# RX08-.net
KiCad netlist of a schematic drawn in EAGLE
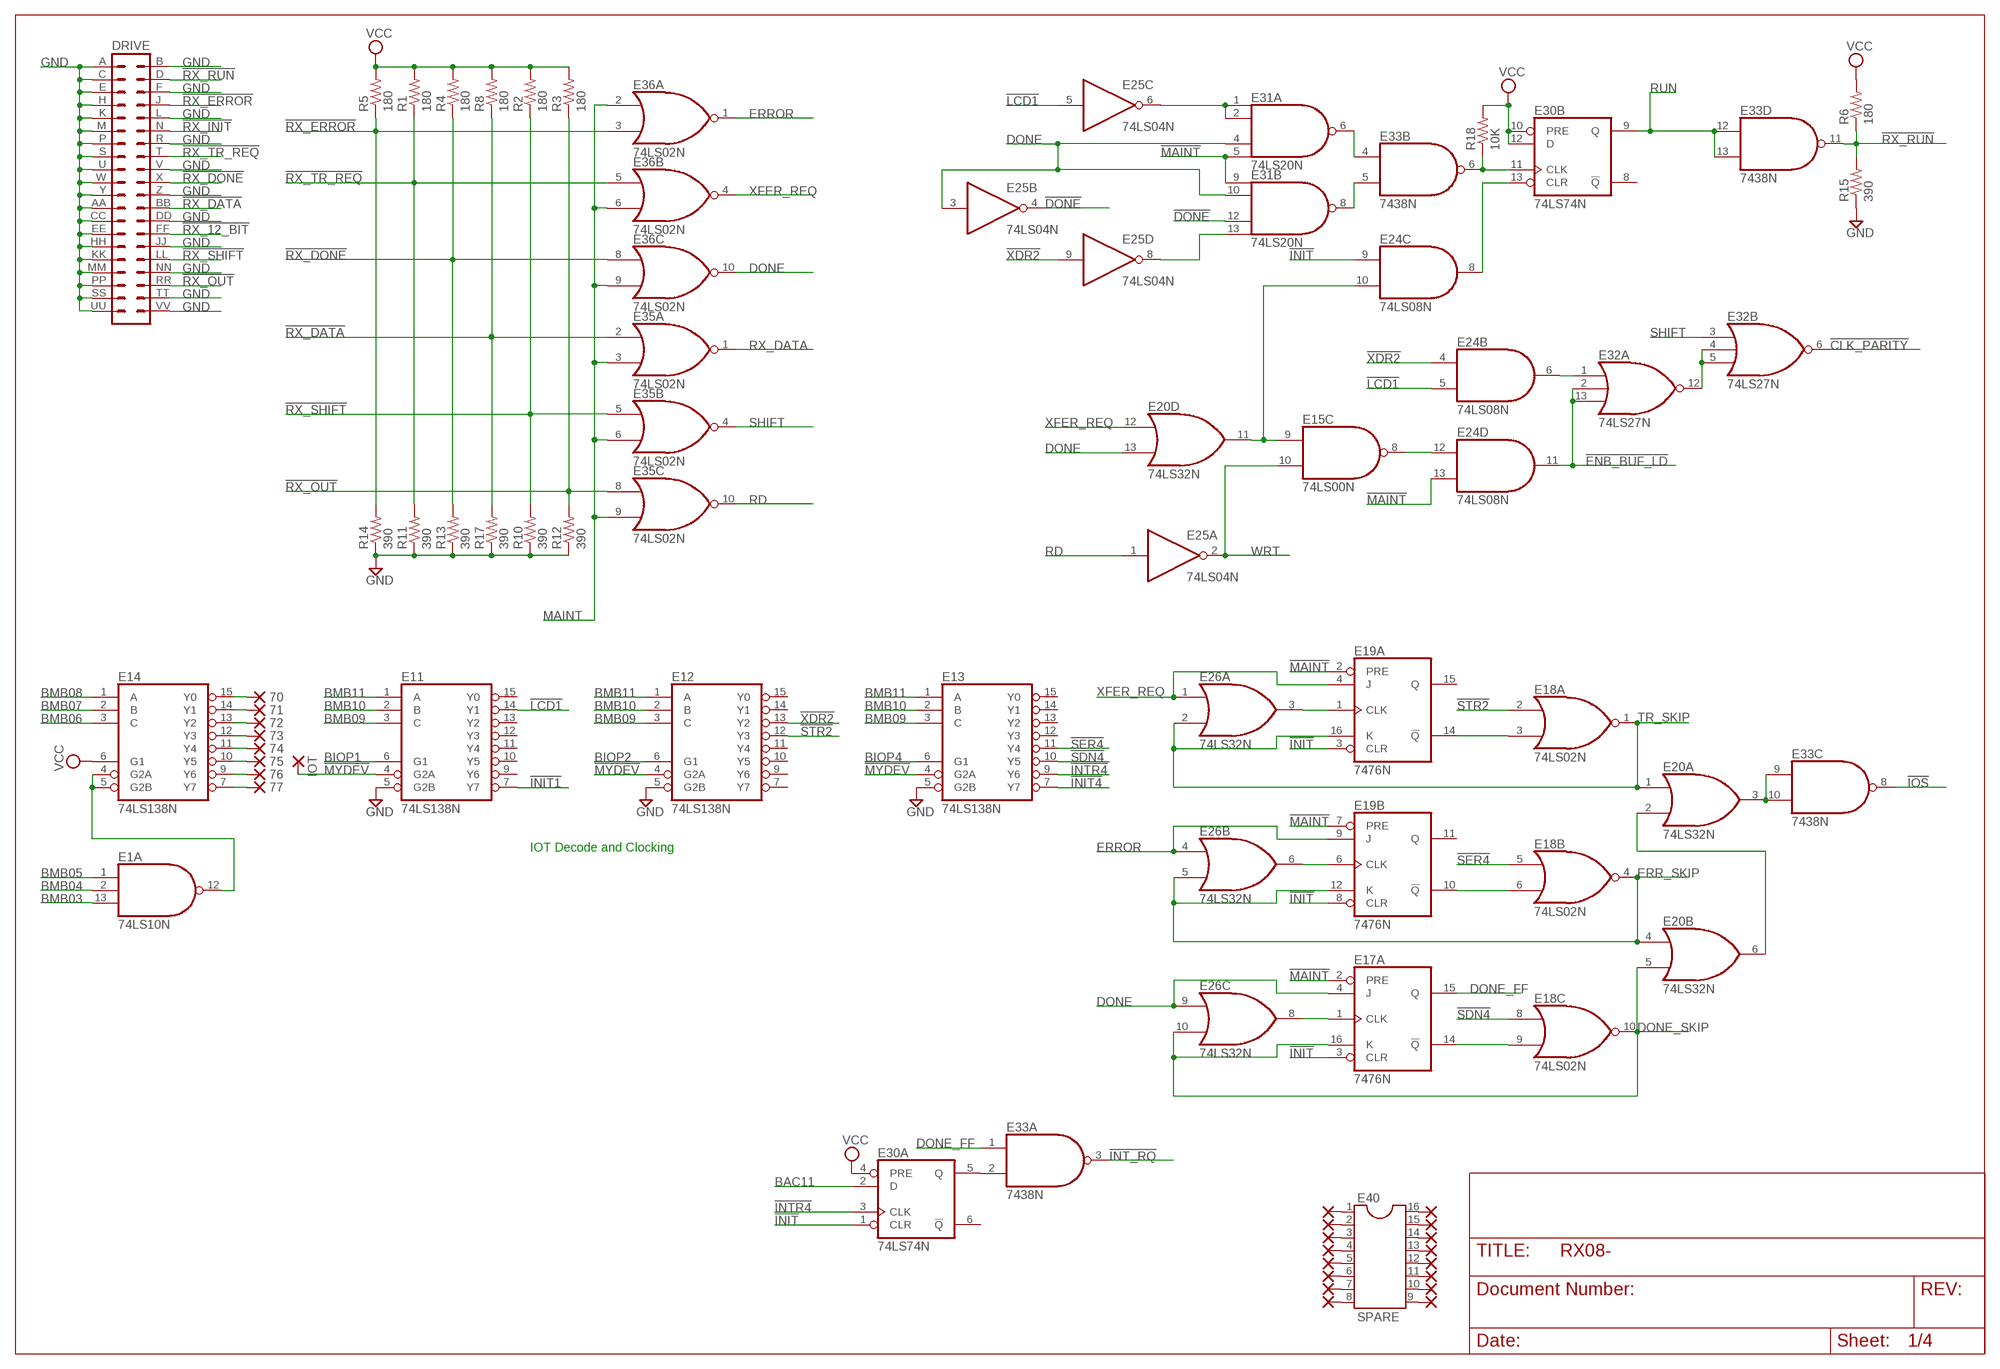
[diagram p0: schematic, sheet 1]
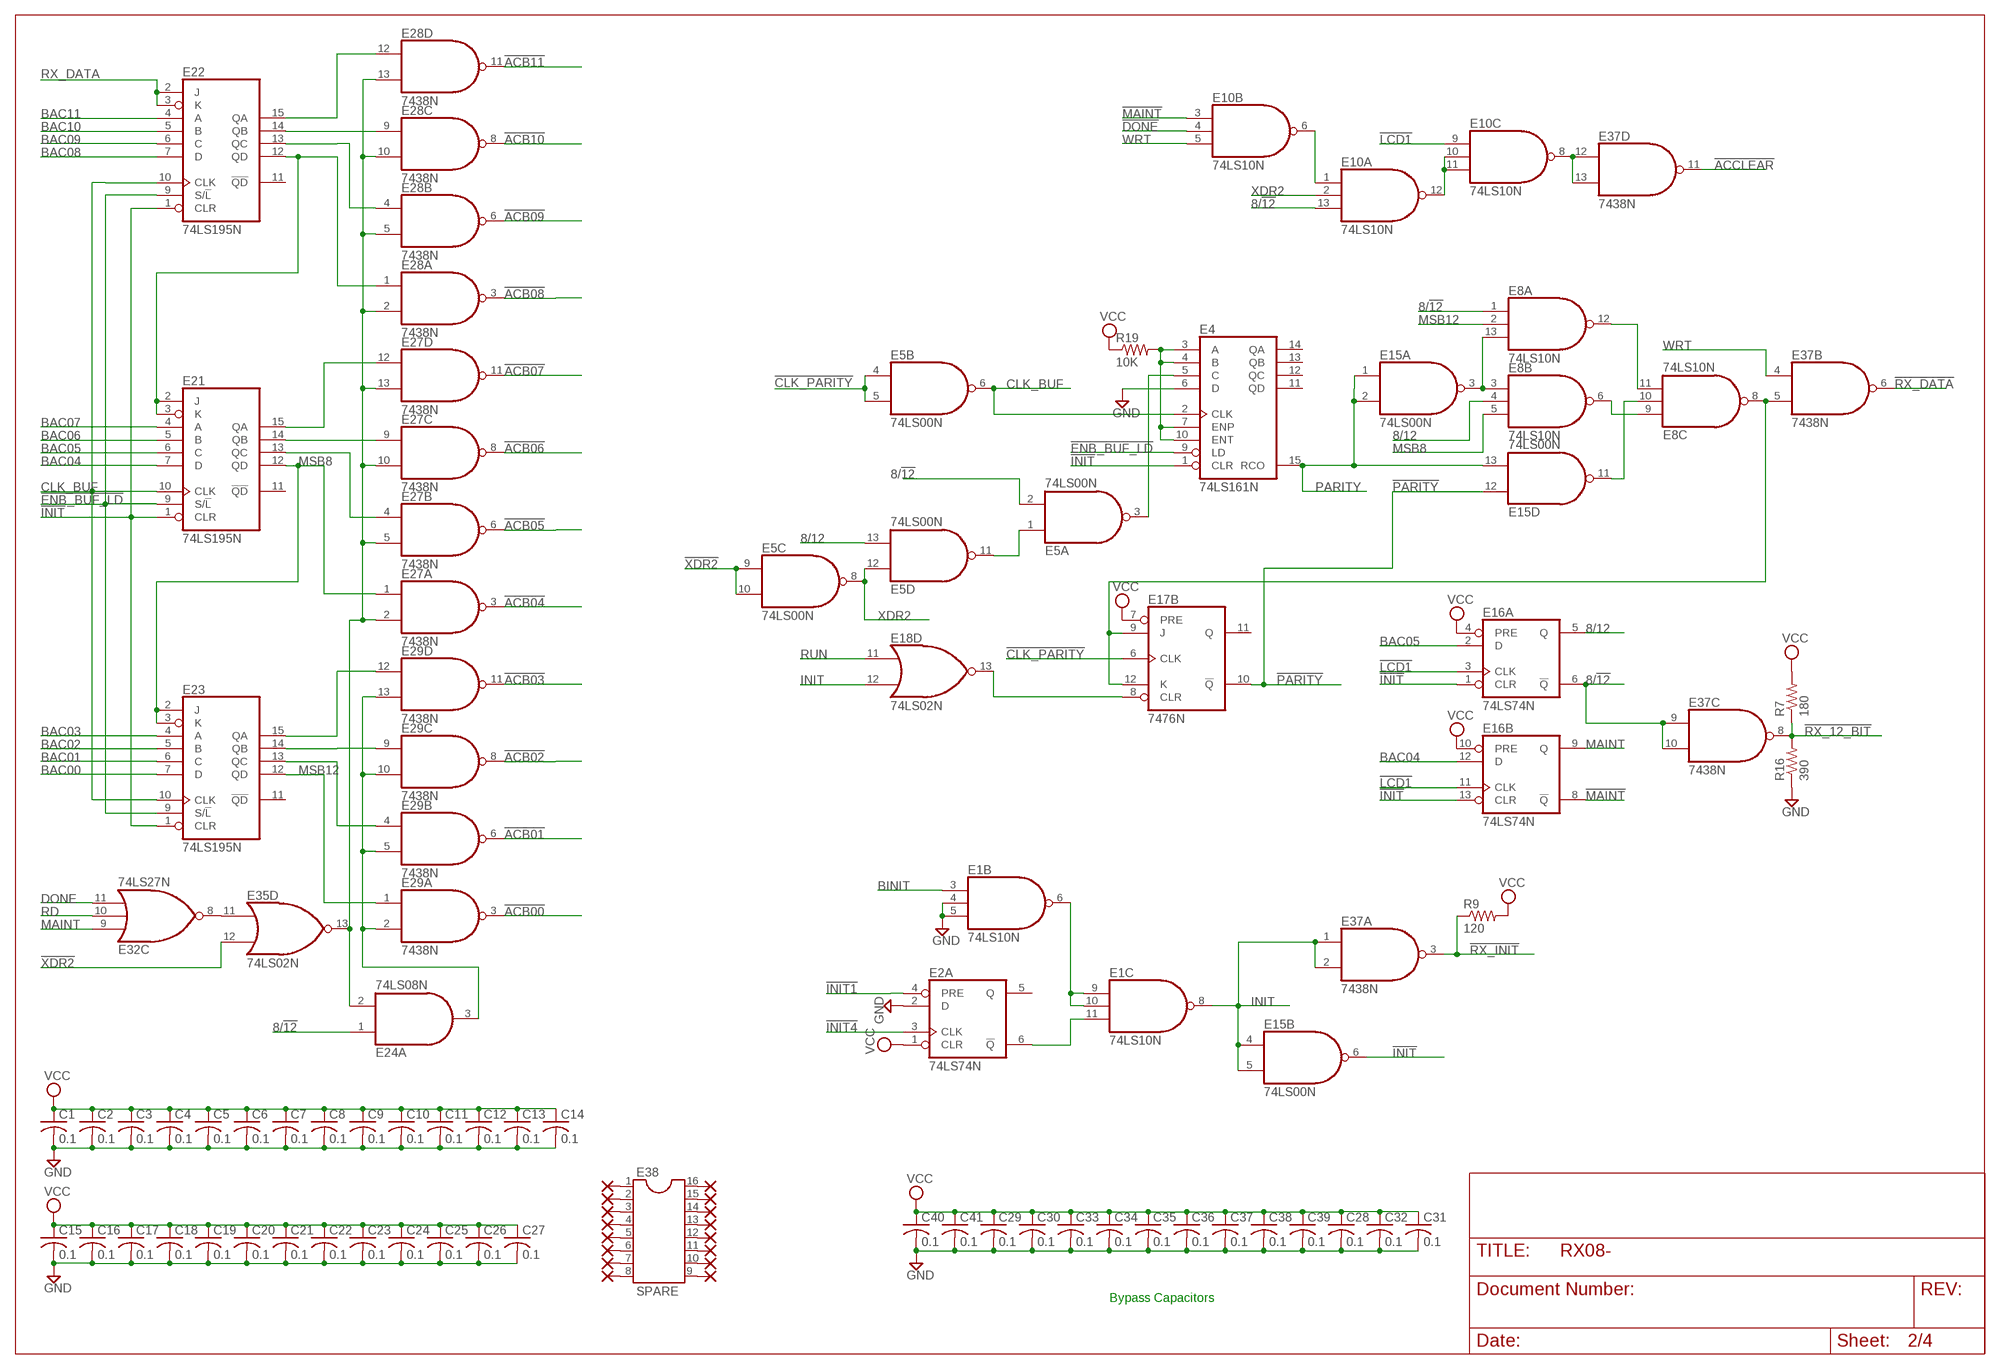
[diagram p1: schematic, sheet 2]
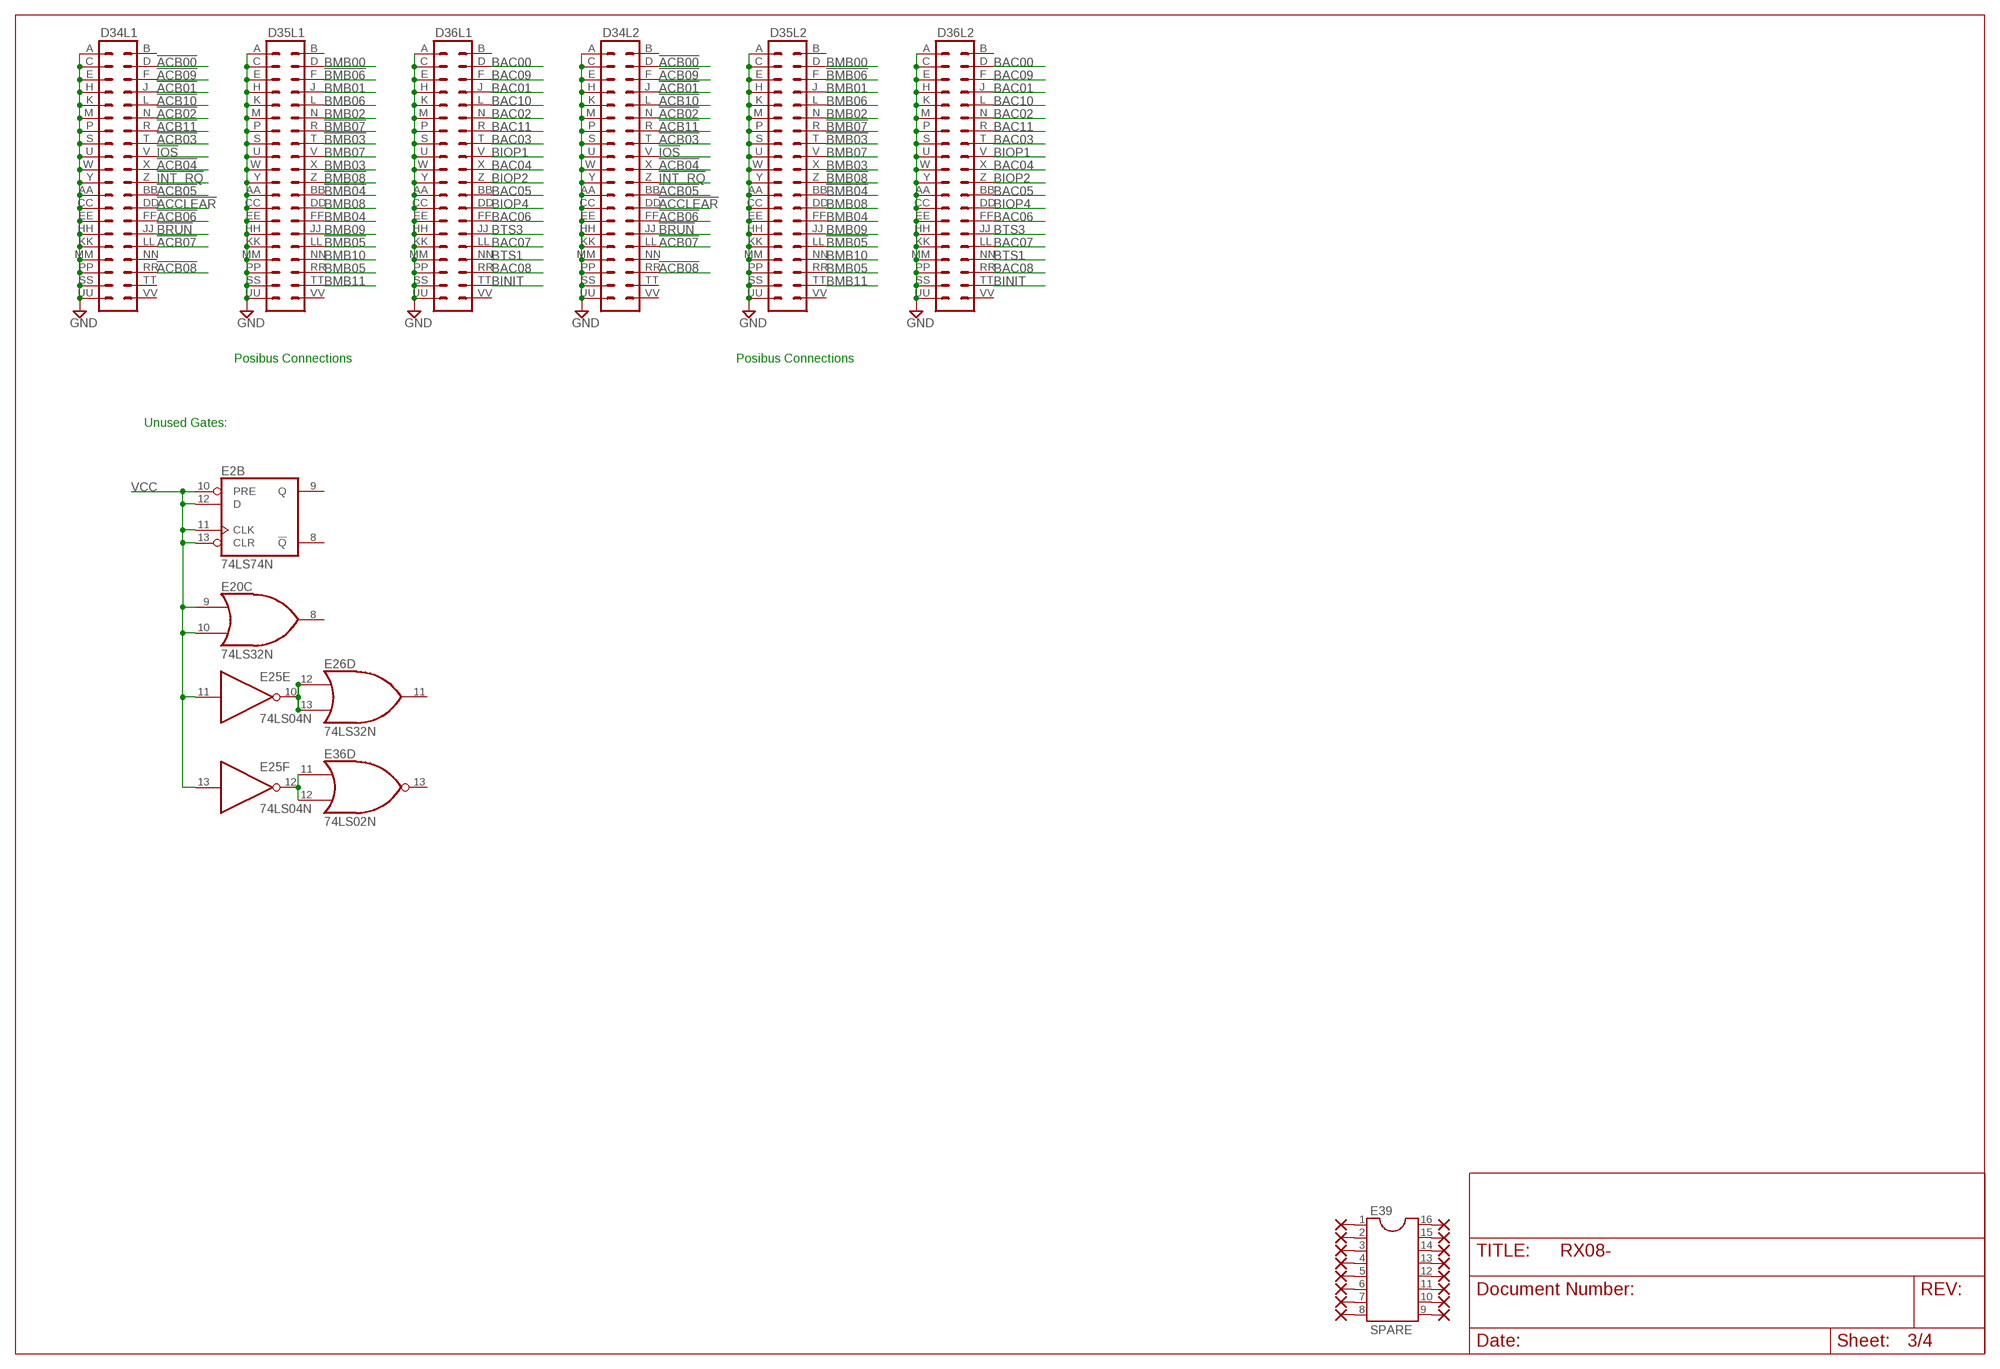
[diagram p2: schematic, sheet 3]
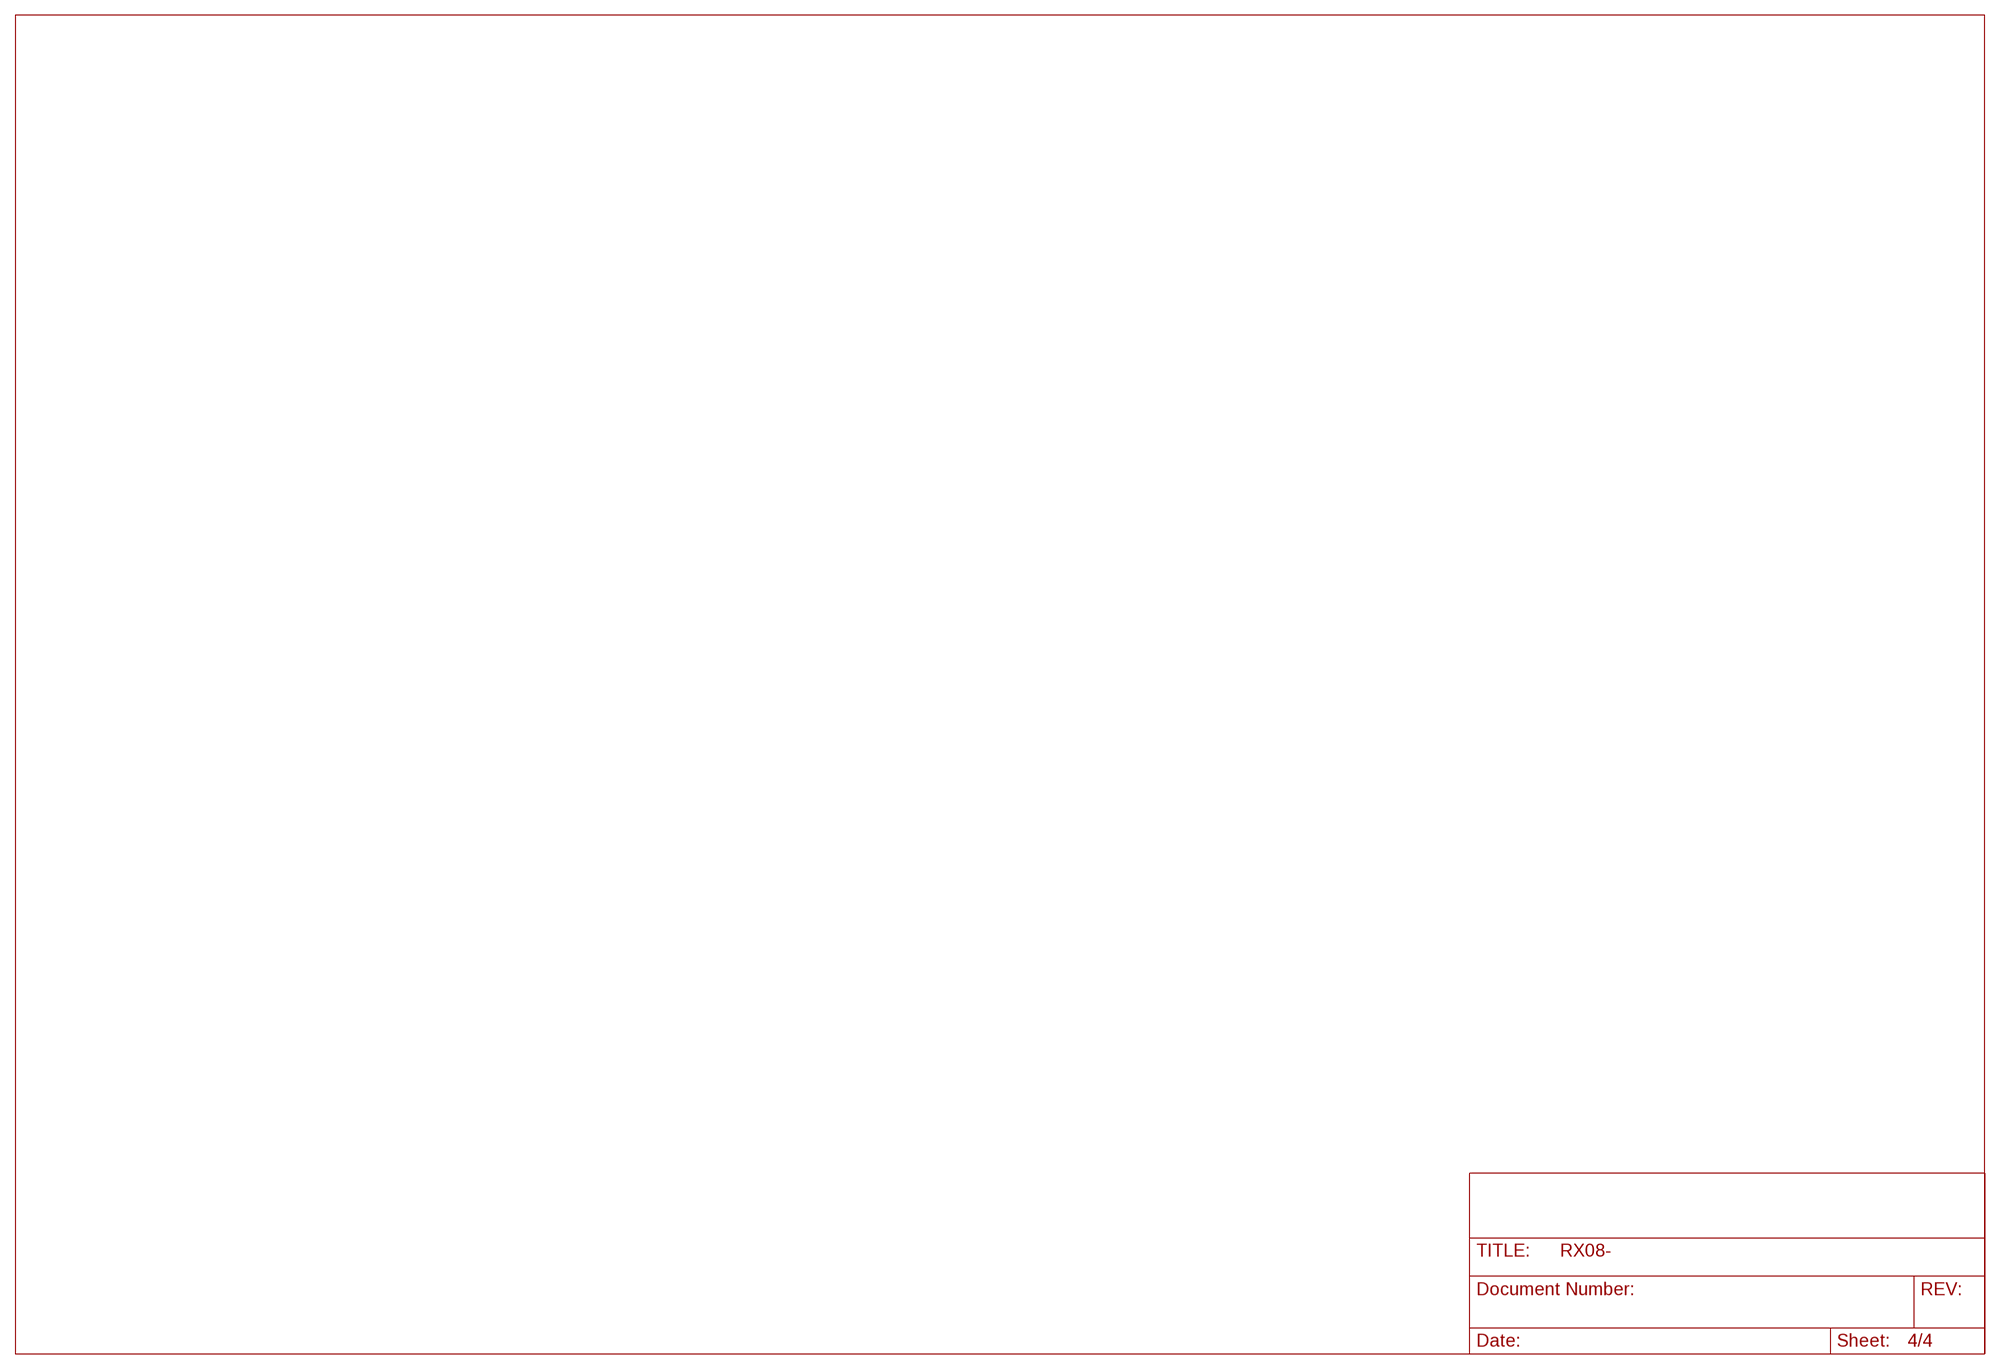
[diagram p3: schematic, sheet 4]

(export (version "E")
  (design (tool "Eeschema 10.0.6"))
  (components
    (comp (ref "70")
      (value "1,6/0,8")
      (footprint "eagle-import:1,6_0,8")
      (libsource (lib "eagle-import") (part "1,6/0,8"))
    )
    (comp (ref "71")
      (value "1,6/0,8")
      (footprint "eagle-import:1,6_0,8")
      (libsource (lib "eagle-import") (part "1,6/0,8"))
    )
    (comp (ref "72")
      (value "1,6/0,8")
      (footprint "eagle-import:1,6_0,8")
      (libsource (lib "eagle-import") (part "1,6/0,8"))
    )
    (comp (ref "73")
      (value "1,6/0,8")
      (footprint "eagle-import:1,6_0,8")
      (libsource (lib "eagle-import") (part "1,6/0,8"))
    )
    (comp (ref "74")
      (value "1,6/0,8")
      (footprint "eagle-import:1,6_0,8")
      (libsource (lib "eagle-import") (part "1,6/0,8"))
    )
    (comp (ref "75")
      (value "1,6/0,8")
      (footprint "eagle-import:1,6_0,8")
      (libsource (lib "eagle-import") (part "1,6/0,8"))
    )
    (comp (ref "76")
      (value "1,6/0,8")
      (footprint "eagle-import:1,6_0,8")
      (libsource (lib "eagle-import") (part "1,6/0,8"))
    )
    (comp (ref "77")
      (value "1,6/0,8")
      (footprint "eagle-import:1,6_0,8")
      (libsource (lib "eagle-import") (part "1,6/0,8"))
    )
    (comp (ref "DRIVE")
      (value "DEC40PINV")
      (footprint "eagle-import:DEC40PINV")
      (libsource (lib "eagle-import") (part "DEC40PINV"))
    )
    (comp (ref "E1")
      (value "74LS10N")
      (footprint "eagle-import:DIL14")
      (libsource (lib "eagle-import") (part "7410NLS"))
    )
    (comp (ref "E11")
      (value "74LS138N")
      (footprint "eagle-import:DIL16")
      (libsource (lib "eagle-import") (part "74138NLS"))
    )
    (comp (ref "E12")
      (value "74LS138N")
      (footprint "eagle-import:DIL16")
      (libsource (lib "eagle-import") (part "74138NLS"))
    )
    (comp (ref "E13")
      (value "74LS138N")
      (footprint "eagle-import:DIL16")
      (libsource (lib "eagle-import") (part "74138NLS"))
    )
    (comp (ref "E14")
      (value "74LS138N")
      (footprint "eagle-import:DIL16")
      (libsource (lib "eagle-import") (part "74138NLS"))
    )
    (comp (ref "E15")
      (value "74LS00N")
      (footprint "eagle-import:DIL14")
      (libsource (lib "eagle-import") (part "7400NLS"))
    )
    (comp (ref "E17")
      (value "7476N")
      (footprint "eagle-import:DIL16")
      (libsource (lib "eagle-import") (part "7476N"))
    )
    (comp (ref "E18")
      (value "74LS02N")
      (footprint "eagle-import:DIL14")
      (libsource (lib "eagle-import") (part "7402NLS"))
    )
    (comp (ref "E19")
      (value "7476N")
      (footprint "eagle-import:DIL16")
      (libsource (lib "eagle-import") (part "7476N"))
    )
    (comp (ref "E20")
      (value "74LS32N")
      (footprint "eagle-import:DIL14")
      (libsource (lib "eagle-import") (part "7432NLS"))
    )
    (comp (ref "E24")
      (value "74LS08N")
      (footprint "eagle-import:DIL14")
      (libsource (lib "eagle-import") (part "7408NLS"))
    )
    (comp (ref "E25")
      (value "74LS04N")
      (footprint "eagle-import:DIL14")
      (libsource (lib "eagle-import") (part "7404NLS"))
    )
    (comp (ref "E26")
      (value "74LS32N")
      (footprint "eagle-import:DIL14")
      (libsource (lib "eagle-import") (part "7432NLS"))
    )
    (comp (ref "E30")
      (value "74LS74N")
      (footprint "eagle-import:DIL14")
      (libsource (lib "eagle-import") (part "7474NLS"))
    )
    (comp (ref "E31")
      (value "74LS20N")
      (footprint "eagle-import:DIL14")
      (libsource (lib "eagle-import") (part "7420NLS"))
    )
    (comp (ref "E32")
      (value "74LS27N")
      (footprint "eagle-import:DIL14")
      (libsource (lib "eagle-import") (part "7427NLS"))
    )
    (comp (ref "E33")
      (value "7438N")
      (footprint "eagle-import:DIL14")
      (libsource (lib "eagle-import") (part "7438N"))
    )
    (comp (ref "E35")
      (value "74LS02N")
      (footprint "eagle-import:DIL14")
      (libsource (lib "eagle-import") (part "7402NLS"))
    )
    (comp (ref "E36")
      (value "74LS02N")
      (footprint "eagle-import:DIL14")
      (libsource (lib "eagle-import") (part "7402NLS"))
    )
    (comp (ref "E40")
      (value "SPARE")
      (footprint "eagle-import:DIL16")
      (libsource (lib "eagle-import") (part "DIL16"))
    )
    (comp (ref "IOT")
      (value "1,6/0,8")
      (footprint "eagle-import:1,6_0,8")
      (libsource (lib "eagle-import") (part "1,6/0,8"))
    )
    (comp (ref "PAD18")
      (value "1,6/0,8")
      (footprint "eagle-import:1,6_0,8")
      (libsource (lib "eagle-import") (part "1,6/0,8"))
    )
    (comp (ref "PAD19")
      (value "1,6/0,8")
      (footprint "eagle-import:1,6_0,8")
      (libsource (lib "eagle-import") (part "1,6/0,8"))
    )
    (comp (ref "PAD28")
      (value "1,6/0,8")
      (footprint "eagle-import:1,6_0,8")
      (libsource (lib "eagle-import") (part "1,6/0,8"))
    )
    (comp (ref "PAD29")
      (value "1,6/0,8")
      (footprint "eagle-import:1,6_0,8")
      (libsource (lib "eagle-import") (part "1,6/0,8"))
    )
    (comp (ref "PAD30")
      (value "1,6/0,8")
      (footprint "eagle-import:1,6_0,8")
      (libsource (lib "eagle-import") (part "1,6/0,8"))
    )
    (comp (ref "PAD31")
      (value "1,6/0,8")
      (footprint "eagle-import:1,6_0,8")
      (libsource (lib "eagle-import") (part "1,6/0,8"))
    )
    (comp (ref "PAD32")
      (value "1,6/0,8")
      (footprint "eagle-import:1,6_0,8")
      (libsource (lib "eagle-import") (part "1,6/0,8"))
    )
    (comp (ref "PAD33")
      (value "1,6/0,8")
      (footprint "eagle-import:1,6_0,8")
      (libsource (lib "eagle-import") (part "1,6/0,8"))
    )
    (comp (ref "PAD34")
      (value "1,6/0,8")
      (footprint "eagle-import:1,6_0,8")
      (libsource (lib "eagle-import") (part "1,6/0,8"))
    )
    (comp (ref "PAD35")
      (value "1,6/0,8")
      (footprint "eagle-import:1,6_0,8")
      (libsource (lib "eagle-import") (part "1,6/0,8"))
    )
    (comp (ref "PAD36")
      (value "1,6/0,8")
      (footprint "eagle-import:1,6_0,8")
      (libsource (lib "eagle-import") (part "1,6/0,8"))
    )
    (comp (ref "PAD37")
      (value "1,6/0,8")
      (footprint "eagle-import:1,6_0,8")
      (libsource (lib "eagle-import") (part "1,6/0,8"))
    )
    (comp (ref "PAD38")
      (value "1,6/0,8")
      (footprint "eagle-import:1,6_0,8")
      (libsource (lib "eagle-import") (part "1,6/0,8"))
    )
    (comp (ref "PAD39")
      (value "1,6/0,8")
      (footprint "eagle-import:1,6_0,8")
      (libsource (lib "eagle-import") (part "1,6/0,8"))
    )
    (comp (ref "PAD40")
      (value "1,6/0,8")
      (footprint "eagle-import:1,6_0,8")
      (libsource (lib "eagle-import") (part "1,6/0,8"))
    )
    (comp (ref "PAD41")
      (value "1,6/0,8")
      (footprint "eagle-import:1,6_0,8")
      (libsource (lib "eagle-import") (part "1,6/0,8"))
    )
    (comp (ref "R1")
      (value "180")
      (footprint "eagle-import:0207_10")
      (libsource (lib "eagle-import") (part "R-US_0207/10"))
    )
    (comp (ref "R2")
      (value "180")
      (footprint "eagle-import:0207_10")
      (libsource (lib "eagle-import") (part "R-US_0207/10"))
    )
    (comp (ref "R3")
      (value "180")
      (footprint "eagle-import:0207_10")
      (libsource (lib "eagle-import") (part "R-US_0207/10"))
    )
    (comp (ref "R4")
      (value "180")
      (footprint "eagle-import:0207_10")
      (libsource (lib "eagle-import") (part "R-US_0207/10"))
    )
    (comp (ref "R5")
      (value "180")
      (footprint "eagle-import:0207_10")
      (libsource (lib "eagle-import") (part "R-US_0207/10"))
    )
    (comp (ref "R6")
      (value "180")
      (footprint "eagle-import:0207_10")
      (libsource (lib "eagle-import") (part "R-US_0207/10"))
    )
    (comp (ref "R8")
      (value "180")
      (footprint "eagle-import:0207_10")
      (libsource (lib "eagle-import") (part "R-US_0207/10"))
    )
    (comp (ref "R10")
      (value "390")
      (footprint "eagle-import:0207_10")
      (libsource (lib "eagle-import") (part "R-US_0207/10"))
    )
    (comp (ref "R11")
      (value "390")
      (footprint "eagle-import:0207_10")
      (libsource (lib "eagle-import") (part "R-US_0207/10"))
    )
    (comp (ref "R12")
      (value "390")
      (footprint "eagle-import:0207_10")
      (libsource (lib "eagle-import") (part "R-US_0207/10"))
    )
    (comp (ref "R13")
      (value "390")
      (footprint "eagle-import:0207_10")
      (libsource (lib "eagle-import") (part "R-US_0207/10"))
    )
    (comp (ref "R14")
      (value "390")
      (footprint "eagle-import:0207_10")
      (libsource (lib "eagle-import") (part "R-US_0207/10"))
    )
    (comp (ref "R15")
      (value "390")
      (footprint "eagle-import:0207_10")
      (libsource (lib "eagle-import") (part "R-US_0207/10"))
    )
    (comp (ref "R17")
      (value "390")
      (footprint "eagle-import:0207_10")
      (libsource (lib "eagle-import") (part "R-US_0207/10"))
    )
    (comp (ref "R18")
      (value "10K")
      (footprint "eagle-import:0207_10")
      (libsource (lib "eagle-import") (part "R-US_0207/10"))
    )
    (comp (ref "C1")
      (value "0.1")
      (footprint "eagle-import:C050-025X075")
      (libsource (lib "eagle-import") (part "C-US050-025X075"))
    )
    (comp (ref "C2")
      (value "0.1")
      (footprint "eagle-import:C050-025X075")
      (libsource (lib "eagle-import") (part "C-US050-025X075"))
    )
    (comp (ref "C3")
      (value "0.1")
      (footprint "eagle-import:C050-025X075")
      (libsource (lib "eagle-import") (part "C-US050-025X075"))
    )
    (comp (ref "C4")
      (value "0.1")
      (footprint "eagle-import:C050-025X075")
      (libsource (lib "eagle-import") (part "C-US050-025X075"))
    )
    (comp (ref "C5")
      (value "0.1")
      (footprint "eagle-import:C050-025X075")
      (libsource (lib "eagle-import") (part "C-US050-025X075"))
    )
    (comp (ref "C6")
      (value "0.1")
      (footprint "eagle-import:C050-025X075")
      (libsource (lib "eagle-import") (part "C-US050-025X075"))
    )
    (comp (ref "C7")
      (value "0.1")
      (footprint "eagle-import:C050-025X075")
      (libsource (lib "eagle-import") (part "C-US050-025X075"))
    )
    (comp (ref "C8")
      (value "0.1")
      (footprint "eagle-import:C050-025X075")
      (libsource (lib "eagle-import") (part "C-US050-025X075"))
    )
    (comp (ref "C9")
      (value "0.1")
      (footprint "eagle-import:C050-025X075")
      (libsource (lib "eagle-import") (part "C-US050-025X075"))
    )
    (comp (ref "C10")
      (value "0.1")
      (footprint "eagle-import:C050-025X075")
      (libsource (lib "eagle-import") (part "C-US050-025X075"))
    )
    (comp (ref "C11")
      (value "0.1")
      (footprint "eagle-import:C050-025X075")
      (libsource (lib "eagle-import") (part "C-US050-025X075"))
    )
    (comp (ref "C12")
      (value "0.1")
      (footprint "eagle-import:C050-025X075")
      (libsource (lib "eagle-import") (part "C-US050-025X075"))
    )
    (comp (ref "C13")
      (value "0.1")
      (footprint "eagle-import:C050-025X075")
      (libsource (lib "eagle-import") (part "C-US050-025X075"))
    )
    (comp (ref "C14")
      (value "0.1")
      (footprint "eagle-import:C050-025X075")
      (libsource (lib "eagle-import") (part "C-US050-025X075"))
    )
    (comp (ref "C15")
      (value "0.1")
      (footprint "eagle-import:C050-025X075")
      (libsource (lib "eagle-import") (part "C-US050-025X075"))
    )
    (comp (ref "C16")
      (value "0.1")
      (footprint "eagle-import:C050-025X075")
      (libsource (lib "eagle-import") (part "C-US050-025X075"))
    )
    (comp (ref "C17")
      (value "0.1")
      (footprint "eagle-import:C050-025X075")
      (libsource (lib "eagle-import") (part "C-US050-025X075"))
    )
    (comp (ref "C18")
      (value "0.1")
      (footprint "eagle-import:C050-025X075")
      (libsource (lib "eagle-import") (part "C-US050-025X075"))
    )
    (comp (ref "C19")
      (value "0.1")
      (footprint "eagle-import:C050-025X075")
      (libsource (lib "eagle-import") (part "C-US050-025X075"))
    )
    (comp (ref "C20")
      (value "0.1")
      (footprint "eagle-import:C050-025X075")
      (libsource (lib "eagle-import") (part "C-US050-025X075"))
    )
    (comp (ref "C21")
      (value "0.1")
      (footprint "eagle-import:C050-025X075")
      (libsource (lib "eagle-import") (part "C-US050-025X075"))
    )
    (comp (ref "C22")
      (value "0.1")
      (footprint "eagle-import:C050-025X075")
      (libsource (lib "eagle-import") (part "C-US050-025X075"))
    )
    (comp (ref "C23")
      (value "0.1")
      (footprint "eagle-import:C050-025X075")
      (libsource (lib "eagle-import") (part "C-US050-025X075"))
    )
    (comp (ref "C24")
      (value "0.1")
      (footprint "eagle-import:C050-025X075")
      (libsource (lib "eagle-import") (part "C-US050-025X075"))
    )
    (comp (ref "C25")
      (value "0.1")
      (footprint "eagle-import:C050-025X075")
      (libsource (lib "eagle-import") (part "C-US050-025X075"))
    )
    (comp (ref "C26")
      (value "0.1")
      (footprint "eagle-import:C050-025X075")
      (libsource (lib "eagle-import") (part "C-US050-025X075"))
    )
    (comp (ref "C27")
      (value "0.1")
      (footprint "eagle-import:C050-025X075")
      (libsource (lib "eagle-import") (part "C-US050-025X075"))
    )
    (comp (ref "C28")
      (value "0.1")
      (footprint "eagle-import:C050-025X075")
      (libsource (lib "eagle-import") (part "C-US050-025X075"))
    )
    (comp (ref "C29")
      (value "0.1")
      (footprint "eagle-import:C050-025X075")
      (libsource (lib "eagle-import") (part "C-US050-025X075"))
    )
    (comp (ref "C30")
      (value "0.1")
      (footprint "eagle-import:C050-025X075")
      (libsource (lib "eagle-import") (part "C-US050-025X075"))
    )
    (comp (ref "C31")
      (value "0.1")
      (footprint "eagle-import:C050-025X075")
      (libsource (lib "eagle-import") (part "C-US050-025X075"))
    )
    (comp (ref "C32")
      (value "0.1")
      (footprint "eagle-import:C050-025X075")
      (libsource (lib "eagle-import") (part "C-US050-025X075"))
    )
    (comp (ref "C33")
      (value "0.1")
      (footprint "eagle-import:C050-025X075")
      (libsource (lib "eagle-import") (part "C-US050-025X075"))
    )
    (comp (ref "C34")
      (value "0.1")
      (footprint "eagle-import:C050-025X075")
      (libsource (lib "eagle-import") (part "C-US050-025X075"))
    )
    (comp (ref "C35")
      (value "0.1")
      (footprint "eagle-import:C050-025X075")
      (libsource (lib "eagle-import") (part "C-US050-025X075"))
    )
    (comp (ref "C36")
      (value "0.1")
      (footprint "eagle-import:C050-025X075")
      (libsource (lib "eagle-import") (part "C-US050-025X075"))
    )
    (comp (ref "C37")
      (value "0.1")
      (footprint "eagle-import:C050-025X075")
      (libsource (lib "eagle-import") (part "C-US050-025X075"))
    )
    (comp (ref "C38")
      (value "0.1")
      (footprint "eagle-import:C050-025X075")
      (libsource (lib "eagle-import") (part "C-US050-025X075"))
    )
    (comp (ref "C39")
      (value "0.1")
      (footprint "eagle-import:C050-025X075")
      (libsource (lib "eagle-import") (part "C-US050-025X075"))
    )
    (comp (ref "C40")
      (value "0.1")
      (footprint "eagle-import:C050-025X075")
      (libsource (lib "eagle-import") (part "C-US050-025X075"))
    )
    (comp (ref "C41")
      (value "0.1")
      (footprint "eagle-import:C050-025X075")
      (libsource (lib "eagle-import") (part "C-US050-025X075"))
    )
    (comp (ref "E2")
      (value "74LS74N")
      (footprint "eagle-import:DIL14")
      (libsource (lib "eagle-import") (part "7474NLS"))
    )
    (comp (ref "E4")
      (value "74LS161N")
      (footprint "eagle-import:DIL16")
      (libsource (lib "eagle-import") (part "74161NLS"))
    )
    (comp (ref "E5")
      (value "74LS00N")
      (footprint "eagle-import:DIL14")
      (libsource (lib "eagle-import") (part "7400NLS"))
    )
    (comp (ref "E8")
      (value "74LS10N")
      (footprint "eagle-import:DIL14")
      (libsource (lib "eagle-import") (part "7410NLS"))
    )
    (comp (ref "E10")
      (value "74LS10N")
      (footprint "eagle-import:DIL14")
      (libsource (lib "eagle-import") (part "7410NLS"))
    )
    (comp (ref "E16")
      (value "74LS74N")
      (footprint "eagle-import:DIL14")
      (libsource (lib "eagle-import") (part "7474NLS"))
    )
    (comp (ref "E21")
      (value "74LS195N")
      (footprint "eagle-import:DIL16")
      (libsource (lib "eagle-import") (part "74195NLS"))
    )
    (comp (ref "E22")
      (value "74LS195N")
      (footprint "eagle-import:DIL16")
      (libsource (lib "eagle-import") (part "74195NLS"))
    )
    (comp (ref "E23")
      (value "74LS195N")
      (footprint "eagle-import:DIL16")
      (libsource (lib "eagle-import") (part "74195NLS"))
    )
    (comp (ref "E27")
      (value "7438N")
      (footprint "eagle-import:DIL14")
      (libsource (lib "eagle-import") (part "7438N"))
    )
    (comp (ref "E28")
      (value "7438N")
      (footprint "eagle-import:DIL14")
      (libsource (lib "eagle-import") (part "7438N"))
    )
    (comp (ref "E29")
      (value "7438N")
      (footprint "eagle-import:DIL14")
      (libsource (lib "eagle-import") (part "7438N"))
    )
    (comp (ref "E37")
      (value "7438N")
      (footprint "eagle-import:DIL14")
      (libsource (lib "eagle-import") (part "7438N"))
    )
    (comp (ref "E38")
      (value "SPARE")
      (footprint "eagle-import:DIL16")
      (libsource (lib "eagle-import") (part "DIL16"))
    )
    (comp (ref "PAD10")
      (value "1,6/0,8")
      (footprint "eagle-import:1,6_0,8")
      (libsource (lib "eagle-import") (part "1,6/0,8"))
    )
    (comp (ref "PAD11")
      (value "1,6/0,8")
      (footprint "eagle-import:1,6_0,8")
      (libsource (lib "eagle-import") (part "1,6/0,8"))
    )
    (comp (ref "PAD12")
      (value "1,6/0,8")
      (footprint "eagle-import:1,6_0,8")
      (libsource (lib "eagle-import") (part "1,6/0,8"))
    )
    (comp (ref "PAD13")
      (value "1,6/0,8")
      (footprint "eagle-import:1,6_0,8")
      (libsource (lib "eagle-import") (part "1,6/0,8"))
    )
    (comp (ref "PAD14")
      (value "1,6/0,8")
      (footprint "eagle-import:1,6_0,8")
      (libsource (lib "eagle-import") (part "1,6/0,8"))
    )
    (comp (ref "PAD15")
      (value "1,6/0,8")
      (footprint "eagle-import:1,6_0,8")
      (libsource (lib "eagle-import") (part "1,6/0,8"))
    )
    (comp (ref "PAD16")
      (value "1,6/0,8")
      (footprint "eagle-import:1,6_0,8")
      (libsource (lib "eagle-import") (part "1,6/0,8"))
    )
    (comp (ref "PAD17")
      (value "1,6/0,8")
      (footprint "eagle-import:1,6_0,8")
      (libsource (lib "eagle-import") (part "1,6/0,8"))
    )
    (comp (ref "PAD20")
      (value "1,6/0,8")
      (footprint "eagle-import:1,6_0,8")
      (libsource (lib "eagle-import") (part "1,6/0,8"))
    )
    (comp (ref "PAD21")
      (value "1,6/0,8")
      (footprint "eagle-import:1,6_0,8")
      (libsource (lib "eagle-import") (part "1,6/0,8"))
    )
    (comp (ref "PAD22")
      (value "1,6/0,8")
      (footprint "eagle-import:1,6_0,8")
      (libsource (lib "eagle-import") (part "1,6/0,8"))
    )
    (comp (ref "PAD23")
      (value "1,6/0,8")
      (footprint "eagle-import:1,6_0,8")
      (libsource (lib "eagle-import") (part "1,6/0,8"))
    )
    (comp (ref "PAD24")
      (value "1,6/0,8")
      (footprint "eagle-import:1,6_0,8")
      (libsource (lib "eagle-import") (part "1,6/0,8"))
    )
    (comp (ref "PAD25")
      (value "1,6/0,8")
      (footprint "eagle-import:1,6_0,8")
      (libsource (lib "eagle-import") (part "1,6/0,8"))
    )
    (comp (ref "PAD26")
      (value "1,6/0,8")
      (footprint "eagle-import:1,6_0,8")
      (libsource (lib "eagle-import") (part "1,6/0,8"))
    )
    (comp (ref "PAD27")
      (value "1,6/0,8")
      (footprint "eagle-import:1,6_0,8")
      (libsource (lib "eagle-import") (part "1,6/0,8"))
    )
    (comp (ref "R7")
      (value "180")
      (footprint "eagle-import:0207_10")
      (libsource (lib "eagle-import") (part "R-US_0207/10"))
    )
    (comp (ref "R9")
      (value "120")
      (footprint "eagle-import:0207_10")
      (libsource (lib "eagle-import") (part "R-US_0207/10"))
    )
    (comp (ref "R16")
      (value "390")
      (footprint "eagle-import:0207_10")
      (libsource (lib "eagle-import") (part "R-US_0207/10"))
    )
    (comp (ref "R19")
      (value "10K")
      (footprint "eagle-import:0207_10")
      (libsource (lib "eagle-import") (part "R-US_0207/10"))
    )
    (comp (ref "D34L1")
      (value "DEC40PINV")
      (footprint "eagle-import:DEC40PINV")
      (libsource (lib "eagle-import") (part "DEC40PINV"))
    )
    (comp (ref "D34L2")
      (value "DEC40PINV")
      (footprint "eagle-import:DEC40PINV")
      (libsource (lib "eagle-import") (part "DEC40PINV"))
    )
    (comp (ref "D35L1")
      (value "DEC40PINV")
      (footprint "eagle-import:DEC40PINV")
      (libsource (lib "eagle-import") (part "DEC40PINV"))
    )
    (comp (ref "D35L2")
      (value "DEC40PINV")
      (footprint "eagle-import:DEC40PINV")
      (libsource (lib "eagle-import") (part "DEC40PINV"))
    )
    (comp (ref "D36L1")
      (value "DEC40PINV")
      (footprint "eagle-import:DEC40PINV")
      (libsource (lib "eagle-import") (part "DEC40PINV"))
    )
    (comp (ref "D36L2")
      (value "DEC40PINV")
      (footprint "eagle-import:DEC40PINV")
      (libsource (lib "eagle-import") (part "DEC40PINV"))
    )
    (comp (ref "E39")
      (value "SPARE")
      (footprint "eagle-import:DIL16")
      (libsource (lib "eagle-import") (part "DIL16"))
    )
    (comp (ref "PAD42")
      (value "1,6/0,8")
      (footprint "eagle-import:1,6_0,8")
      (libsource (lib "eagle-import") (part "1,6/0,8"))
    )
    (comp (ref "PAD43")
      (value "1,6/0,8")
      (footprint "eagle-import:1,6_0,8")
      (libsource (lib "eagle-import") (part "1,6/0,8"))
    )
    (comp (ref "PAD44")
      (value "1,6/0,8")
      (footprint "eagle-import:1,6_0,8")
      (libsource (lib "eagle-import") (part "1,6/0,8"))
    )
    (comp (ref "PAD45")
      (value "1,6/0,8")
      (footprint "eagle-import:1,6_0,8")
      (libsource (lib "eagle-import") (part "1,6/0,8"))
    )
    (comp (ref "PAD46")
      (value "1,6/0,8")
      (footprint "eagle-import:1,6_0,8")
      (libsource (lib "eagle-import") (part "1,6/0,8"))
    )
    (comp (ref "PAD47")
      (value "1,6/0,8")
      (footprint "eagle-import:1,6_0,8")
      (libsource (lib "eagle-import") (part "1,6/0,8"))
    )
    (comp (ref "PAD48")
      (value "1,6/0,8")
      (footprint "eagle-import:1,6_0,8")
      (libsource (lib "eagle-import") (part "1,6/0,8"))
    )
    (comp (ref "PAD49")
      (value "1,6/0,8")
      (footprint "eagle-import:1,6_0,8")
      (libsource (lib "eagle-import") (part "1,6/0,8"))
    )
    (comp (ref "PAD50")
      (value "1,6/0,8")
      (footprint "eagle-import:1,6_0,8")
      (libsource (lib "eagle-import") (part "1,6/0,8"))
    )
    (comp (ref "PAD51")
      (value "1,6/0,8")
      (footprint "eagle-import:1,6_0,8")
      (libsource (lib "eagle-import") (part "1,6/0,8"))
    )
    (comp (ref "PAD52")
      (value "1,6/0,8")
      (footprint "eagle-import:1,6_0,8")
      (libsource (lib "eagle-import") (part "1,6/0,8"))
    )
    (comp (ref "PAD53")
      (value "1,6/0,8")
      (footprint "eagle-import:1,6_0,8")
      (libsource (lib "eagle-import") (part "1,6/0,8"))
    )
    (comp (ref "PAD54")
      (value "1,6/0,8")
      (footprint "eagle-import:1,6_0,8")
      (libsource (lib "eagle-import") (part "1,6/0,8"))
    )
    (comp (ref "PAD55")
      (value "1,6/0,8")
      (footprint "eagle-import:1,6_0,8")
      (libsource (lib "eagle-import") (part "1,6/0,8"))
    )
    (comp (ref "PAD56")
      (value "1,6/0,8")
      (footprint "eagle-import:1,6_0,8")
      (libsource (lib "eagle-import") (part "1,6/0,8"))
    )
    (comp (ref "PAD57")
      (value "1,6/0,8")
      (footprint "eagle-import:1,6_0,8")
      (libsource (lib "eagle-import") (part "1,6/0,8"))
    )
  )
  (nets
    (net (code "1") (name "8{slash}12") (class "Default")
      (node (ref "E16") (pin "5") (pinfunction "Q_5") (pintype "output"))
      (node (ref "E5") (pin "13") (pinfunction "I1_13") (pintype "input"))
      (node (ref "E8") (pin "4") (pinfunction "I1_4") (pintype "input"))
    )
    (net (code "2") (name "8{slash}~{12}") (class "Default")
      (node (ref "E10") (pin "13") (pinfunction "I2_13") (pintype "input"))
      (node (ref "E16") (pin "6") (pinfunction "~{Q}_6") (pintype "output"))
      (node (ref "E24") (pin "1") (pinfunction "I0_1") (pintype "input"))
      (node (ref "E37") (pin "10") (pinfunction "I1_10") (pintype "input"))
      (node (ref "E37") (pin "9") (pinfunction "I0_9") (pintype "input"))
      (node (ref "E5") (pin "2") (pinfunction "I1_2") (pintype "input"))
      (node (ref "E8") (pin "1") (pinfunction "I0_1") (pintype "input"))
    )
    (net (code "3") (name "BAC00") (class "Default")
      (node (ref "D36L1") (pin "D") (pinfunction "4_D") (pintype "bidirectional"))
      (node (ref "D36L2") (pin "D") (pinfunction "4_D") (pintype "bidirectional"))
      (node (ref "E23") (pin "7") (pinfunction "D_7") (pintype "input"))
    )
    (net (code "4") (name "BAC01") (class "Default")
      (node (ref "D36L1") (pin "J") (pinfunction "8_J") (pintype "bidirectional"))
      (node (ref "D36L2") (pin "J") (pinfunction "8_J") (pintype "bidirectional"))
      (node (ref "E23") (pin "6") (pinfunction "C_6") (pintype "input"))
    )
    (net (code "5") (name "BAC02") (class "Default")
      (node (ref "D36L1") (pin "N") (pinfunction "12_N") (pintype "bidirectional"))
      (node (ref "D36L2") (pin "N") (pinfunction "12_N") (pintype "bidirectional"))
      (node (ref "E23") (pin "5") (pinfunction "B_5") (pintype "input"))
    )
    (net (code "6") (name "BAC03") (class "Default")
      (node (ref "D36L1") (pin "T") (pinfunction "16_T") (pintype "bidirectional"))
      (node (ref "D36L2") (pin "T") (pinfunction "16_T") (pintype "bidirectional"))
      (node (ref "E23") (pin "4") (pinfunction "A_4") (pintype "input"))
    )
    (net (code "7") (name "BAC04") (class "Default")
      (node (ref "D36L1") (pin "X") (pinfunction "20_X") (pintype "bidirectional"))
      (node (ref "D36L2") (pin "X") (pinfunction "20_X") (pintype "bidirectional"))
      (node (ref "E16") (pin "12") (pinfunction "D_12") (pintype "input"))
      (node (ref "E21") (pin "7") (pinfunction "D_7") (pintype "input"))
    )
    (net (code "8") (name "BAC05") (class "Default")
      (node (ref "D36L1") (pin "BB") (pinfunction "24_BB") (pintype "bidirectional"))
      (node (ref "D36L2") (pin "BB") (pinfunction "24_BB") (pintype "bidirectional"))
      (node (ref "E16") (pin "2") (pinfunction "D_2") (pintype "input"))
      (node (ref "E21") (pin "6") (pinfunction "C_6") (pintype "input"))
    )
    (net (code "9") (name "BAC06") (class "Default")
      (node (ref "D36L1") (pin "FF") (pinfunction "28_FF") (pintype "bidirectional"))
      (node (ref "D36L2") (pin "FF") (pinfunction "28_FF") (pintype "bidirectional"))
      (node (ref "E21") (pin "5") (pinfunction "B_5") (pintype "input"))
    )
    (net (code "10") (name "BAC07") (class "Default")
      (node (ref "D36L1") (pin "LL") (pinfunction "32_LL") (pintype "bidirectional"))
      (node (ref "D36L2") (pin "LL") (pinfunction "32_LL") (pintype "bidirectional"))
      (node (ref "E21") (pin "4") (pinfunction "A_4") (pintype "input"))
    )
    (net (code "11") (name "BAC08") (class "Default")
      (node (ref "D36L1") (pin "RR") (pinfunction "36_RR") (pintype "bidirectional"))
      (node (ref "D36L2") (pin "RR") (pinfunction "36_RR") (pintype "bidirectional"))
      (node (ref "E22") (pin "7") (pinfunction "D_7") (pintype "input"))
    )
    (net (code "12") (name "BAC09") (class "Default")
      (node (ref "D36L1") (pin "F") (pinfunction "6_F") (pintype "bidirectional"))
      (node (ref "D36L2") (pin "F") (pinfunction "6_F") (pintype "bidirectional"))
      (node (ref "E22") (pin "6") (pinfunction "C_6") (pintype "input"))
    )
    (net (code "13") (name "BAC10") (class "Default")
      (node (ref "D36L1") (pin "L") (pinfunction "10_L") (pintype "bidirectional"))
      (node (ref "D36L2") (pin "L") (pinfunction "10_L") (pintype "bidirectional"))
      (node (ref "E22") (pin "5") (pinfunction "B_5") (pintype "input"))
    )
    (net (code "14") (name "BAC11") (class "Default")
      (node (ref "D36L1") (pin "R") (pinfunction "14_R") (pintype "bidirectional"))
      (node (ref "D36L2") (pin "R") (pinfunction "14_R") (pintype "bidirectional"))
      (node (ref "E22") (pin "4") (pinfunction "A_4") (pintype "input"))
      (node (ref "E30") (pin "2") (pinfunction "D_2") (pintype "input"))
    )
    (net (code "15") (name "BINIT") (class "Default")
      (node (ref "D36L1") (pin "TT") (pinfunction "38_TT") (pintype "bidirectional"))
      (node (ref "D36L2") (pin "TT") (pinfunction "38_TT") (pintype "bidirectional"))
      (node (ref "E1") (pin "3") (pinfunction "I0_3") (pintype "input"))
    )
    (net (code "16") (name "BIOP1") (class "Default")
      (node (ref "D36L1") (pin "V") (pinfunction "18_V") (pintype "bidirectional"))
      (node (ref "D36L2") (pin "V") (pinfunction "18_V") (pintype "bidirectional"))
      (node (ref "E11") (pin "6") (pinfunction "G1_6") (pintype "input"))
    )
    (net (code "17") (name "BIOP2") (class "Default")
      (node (ref "D36L1") (pin "Z") (pinfunction "22_Z") (pintype "bidirectional"))
      (node (ref "D36L2") (pin "Z") (pinfunction "22_Z") (pintype "bidirectional"))
      (node (ref "E12") (pin "6") (pinfunction "G1_6") (pintype "input"))
    )
    (net (code "18") (name "BIOP4") (class "Default")
      (node (ref "D36L1") (pin "DD") (pinfunction "26_DD") (pintype "bidirectional"))
      (node (ref "D36L2") (pin "DD") (pinfunction "26_DD") (pintype "bidirectional"))
      (node (ref "E13") (pin "6") (pinfunction "G1_6") (pintype "input"))
    )
    (net (code "19") (name "BMB00") (class "Default")
      (node (ref "D35L1") (pin "D") (pinfunction "4_D") (pintype "bidirectional"))
      (node (ref "D35L2") (pin "D") (pinfunction "4_D") (pintype "bidirectional"))
    )
    (net (code "20") (name "BMB01") (class "Default")
      (node (ref "D35L1") (pin "J") (pinfunction "8_J") (pintype "bidirectional"))
      (node (ref "D35L2") (pin "J") (pinfunction "8_J") (pintype "bidirectional"))
    )
    (net (code "21") (name "BMB02") (class "Default")
      (node (ref "D35L1") (pin "N") (pinfunction "12_N") (pintype "bidirectional"))
      (node (ref "D35L2") (pin "N") (pinfunction "12_N") (pintype "bidirectional"))
    )
    (net (code "22") (name "BMB03") (class "Default")
      (node (ref "D35L1") (pin "X") (pinfunction "20_X") (pintype "bidirectional"))
      (node (ref "D35L2") (pin "X") (pinfunction "20_X") (pintype "bidirectional"))
      (node (ref "E1") (pin "13") (pinfunction "I2_13") (pintype "input"))
    )
    (net (code "23") (name "BMB04") (class "Default")
      (node (ref "D35L1") (pin "FF") (pinfunction "28_FF") (pintype "bidirectional"))
      (node (ref "D35L2") (pin "FF") (pinfunction "28_FF") (pintype "bidirectional"))
      (node (ref "E1") (pin "2") (pinfunction "I1_2") (pintype "input"))
    )
    (net (code "24") (name "BMB05") (class "Default")
      (node (ref "D35L1") (pin "RR") (pinfunction "36_RR") (pintype "bidirectional"))
      (node (ref "D35L2") (pin "RR") (pinfunction "36_RR") (pintype "bidirectional"))
      (node (ref "E1") (pin "1") (pinfunction "I0_1") (pintype "input"))
    )
    (net (code "25") (name "BMB06") (class "Default")
      (node (ref "D35L1") (pin "L") (pinfunction "10_L") (pintype "bidirectional"))
      (node (ref "D35L2") (pin "L") (pinfunction "10_L") (pintype "bidirectional"))
      (node (ref "E14") (pin "3") (pinfunction "C_3") (pintype "input"))
    )
    (net (code "26") (name "BMB07") (class "Default")
      (node (ref "D35L1") (pin "V") (pinfunction "18_V") (pintype "bidirectional"))
      (node (ref "D35L2") (pin "V") (pinfunction "18_V") (pintype "bidirectional"))
      (node (ref "E14") (pin "2") (pinfunction "B_2") (pintype "input"))
    )
    (net (code "27") (name "BMB08") (class "Default")
      (node (ref "D35L1") (pin "DD") (pinfunction "26_DD") (pintype "bidirectional"))
      (node (ref "D35L2") (pin "DD") (pinfunction "26_DD") (pintype "bidirectional"))
      (node (ref "E14") (pin "1") (pinfunction "A_1") (pintype "input"))
    )
    (net (code "28") (name "BMB09") (class "Default")
      (node (ref "D35L1") (pin "JJ") (pinfunction "30_JJ") (pintype "bidirectional"))
      (node (ref "D35L2") (pin "JJ") (pinfunction "30_JJ") (pintype "bidirectional"))
      (node (ref "E11") (pin "3") (pinfunction "C_3") (pintype "input"))
      (node (ref "E12") (pin "3") (pinfunction "C_3") (pintype "input"))
      (node (ref "E13") (pin "3") (pinfunction "C_3") (pintype "input"))
    )
    (net (code "29") (name "BMB10") (class "Default")
      (node (ref "D35L1") (pin "NN") (pinfunction "34_NN") (pintype "bidirectional"))
      (node (ref "D35L2") (pin "NN") (pinfunction "34_NN") (pintype "bidirectional"))
      (node (ref "E11") (pin "2") (pinfunction "B_2") (pintype "input"))
      (node (ref "E12") (pin "2") (pinfunction "B_2") (pintype "input"))
      (node (ref "E13") (pin "2") (pinfunction "B_2") (pintype "input"))
    )
    (net (code "30") (name "BMB11") (class "Default")
      (node (ref "D35L1") (pin "TT") (pinfunction "38_TT") (pintype "bidirectional"))
      (node (ref "D35L2") (pin "TT") (pinfunction "38_TT") (pintype "bidirectional"))
      (node (ref "E11") (pin "1") (pinfunction "A_1") (pintype "input"))
      (node (ref "E12") (pin "1") (pinfunction "A_1") (pintype "input"))
      (node (ref "E13") (pin "1") (pinfunction "A_1") (pintype "input"))
    )
    (net (code "31") (name "BTS1") (class "Default")
      (node (ref "D36L1") (pin "NN") (pinfunction "34_NN") (pintype "bidirectional"))
      (node (ref "D36L2") (pin "NN") (pinfunction "34_NN") (pintype "bidirectional"))
    )
    (net (code "32") (name "BTS3") (class "Default")
      (node (ref "D36L1") (pin "JJ") (pinfunction "30_JJ") (pintype "bidirectional"))
      (node (ref "D36L2") (pin "JJ") (pinfunction "30_JJ") (pintype "bidirectional"))
    )
    (net (code "33") (name "CLK_BUF") (class "Default")
      (node (ref "E21") (pin "10") (pinfunction "CLK_10") (pintype "input"))
      (node (ref "E22") (pin "10") (pinfunction "CLK_10") (pintype "input"))
      (node (ref "E23") (pin "10") (pinfunction "CLK_10") (pintype "input"))
      (node (ref "E4") (pin "2") (pinfunction "CLK_2") (pintype "input"))
      (node (ref "E5") (pin "6") (pinfunction "O_6") (pintype "output"))
    )
    (net (code "34") (name "DONE") (class "Default")
      (node (ref "E17") (pin "4") (pinfunction "J_4") (pintype "input"))
      (node (ref "E20") (pin "13") (pinfunction "I1_13") (pintype "input"))
      (node (ref "E25") (pin "3") (pinfunction "I_3") (pintype "input"))
      (node (ref "E26") (pin "9") (pinfunction "I0_9") (pintype "input"))
      (node (ref "E31") (pin "10") (pinfunction "I1_10") (pintype "input"))
      (node (ref "E31") (pin "4") (pinfunction "I2_4") (pintype "input"))
      (node (ref "E32") (pin "11") (pinfunction "I2_11") (pintype "input"))
      (node (ref "E36") (pin "10") (pinfunction "O_10") (pintype "output"))
    )
    (net (code "35") (name "DONE_FF") (class "Default")
      (node (ref "E17") (pin "15") (pinfunction "Q_15") (pintype "output"))
      (node (ref "E33") (pin "1") (pinfunction "I0_1") (pintype "input"))
    )
    (net (code "36") (name "DONE_SKIP") (class "Default")
      (node (ref "E17") (pin "16") (pinfunction "K_16") (pintype "input"))
      (node (ref "E18") (pin "10") (pinfunction "O_10") (pintype "output"))
      (node (ref "E20") (pin "5") (pinfunction "I1_5") (pintype "input"))
      (node (ref "E26") (pin "10") (pinfunction "I1_10") (pintype "input"))
    )
    (net (code "37") (name "ERROR") (class "Default")
      (node (ref "E19") (pin "9") (pinfunction "J_9") (pintype "input"))
      (node (ref "E26") (pin "4") (pinfunction "I0_4") (pintype "input"))
      (node (ref "E36") (pin "1") (pinfunction "O_1") (pintype "output"))
    )
    (net (code "38") (name "ERR_SKIP") (class "Default")
      (node (ref "E18") (pin "4") (pinfunction "O_4") (pintype "output"))
      (node (ref "E19") (pin "12") (pinfunction "K_12") (pintype "input"))
      (node (ref "E20") (pin "4") (pinfunction "I0_4") (pintype "input"))
      (node (ref "E26") (pin "5") (pinfunction "I1_5") (pintype "input"))
    )
    (net (code "39") (name "GND") (class "Default")
      (node (ref "C1") (pin "2") (pinfunction "2_2") (pintype "passive"))
      (node (ref "C10") (pin "2") (pinfunction "2_2") (pintype "passive"))
      (node (ref "C11") (pin "2") (pinfunction "2_2") (pintype "passive"))
      (node (ref "C12") (pin "2") (pinfunction "2_2") (pintype "passive"))
      (node (ref "C13") (pin "2") (pinfunction "2_2") (pintype "passive"))
      (node (ref "C14") (pin "2") (pinfunction "2_2") (pintype "passive"))
      (node (ref "C15") (pin "2") (pinfunction "2_2") (pintype "passive"))
      (node (ref "C16") (pin "2") (pinfunction "2_2") (pintype "passive"))
      (node (ref "C17") (pin "2") (pinfunction "2_2") (pintype "passive"))
      (node (ref "C18") (pin "2") (pinfunction "2_2") (pintype "passive"))
      (node (ref "C19") (pin "2") (pinfunction "2_2") (pintype "passive"))
      (node (ref "C2") (pin "2") (pinfunction "2_2") (pintype "passive"))
      (node (ref "C20") (pin "2") (pinfunction "2_2") (pintype "passive"))
      (node (ref "C21") (pin "2") (pinfunction "2_2") (pintype "passive"))
      (node (ref "C22") (pin "2") (pinfunction "2_2") (pintype "passive"))
      (node (ref "C23") (pin "2") (pinfunction "2_2") (pintype "passive"))
      (node (ref "C24") (pin "2") (pinfunction "2_2") (pintype "passive"))
      (node (ref "C25") (pin "2") (pinfunction "2_2") (pintype "passive"))
      (node (ref "C26") (pin "2") (pinfunction "2_2") (pintype "passive"))
      (node (ref "C27") (pin "2") (pinfunction "2_2") (pintype "passive"))
      (node (ref "C28") (pin "2") (pinfunction "2_2") (pintype "passive"))
      (node (ref "C29") (pin "2") (pinfunction "2_2") (pintype "passive"))
      (node (ref "C3") (pin "2") (pinfunction "2_2") (pintype "passive"))
      (node (ref "C30") (pin "2") (pinfunction "2_2") (pintype "passive"))
      (node (ref "C31") (pin "2") (pinfunction "2_2") (pintype "passive"))
      (node (ref "C32") (pin "2") (pinfunction "2_2") (pintype "passive"))
      (node (ref "C33") (pin "2") (pinfunction "2_2") (pintype "passive"))
      (node (ref "C34") (pin "2") (pinfunction "2_2") (pintype "passive"))
      (node (ref "C35") (pin "2") (pinfunction "2_2") (pintype "passive"))
      (node (ref "C36") (pin "2") (pinfunction "2_2") (pintype "passive"))
      (node (ref "C37") (pin "2") (pinfunction "2_2") (pintype "passive"))
      (node (ref "C38") (pin "2") (pinfunction "2_2") (pintype "passive"))
      (node (ref "C39") (pin "2") (pinfunction "2_2") (pintype "passive"))
      (node (ref "C4") (pin "2") (pinfunction "2_2") (pintype "passive"))
      (node (ref "C40") (pin "2") (pinfunction "2_2") (pintype "passive"))
      (node (ref "C41") (pin "2") (pinfunction "2_2") (pintype "passive"))
      (node (ref "C5") (pin "2") (pinfunction "2_2") (pintype "passive"))
      (node (ref "C6") (pin "2") (pinfunction "2_2") (pintype "passive"))
      (node (ref "C7") (pin "2") (pinfunction "2_2") (pintype "passive"))
      (node (ref "C8") (pin "2") (pinfunction "2_2") (pintype "passive"))
      (node (ref "C9") (pin "2") (pinfunction "2_2") (pintype "passive"))
      (node (ref "D34L1") (pin "A") (pinfunction "1_A") (pintype "bidirectional"))
      (node (ref "D34L1") (pin "AA") (pinfunction "23_AA") (pintype "bidirectional"))
      (node (ref "D34L1") (pin "C") (pinfunction "3_C") (pintype "bidirectional"))
      (node (ref "D34L1") (pin "CC") (pinfunction "25_CC") (pintype "bidirectional"))
      (node (ref "D34L1") (pin "E") (pinfunction "5_E") (pintype "bidirectional"))
      (node (ref "D34L1") (pin "EE") (pinfunction "27_EE") (pintype "bidirectional"))
      (node (ref "D34L1") (pin "H") (pinfunction "7_H") (pintype "bidirectional"))
      (node (ref "D34L1") (pin "HH") (pinfunction "29_HH") (pintype "bidirectional"))
      (node (ref "D34L1") (pin "K") (pinfunction "9_K") (pintype "bidirectional"))
      (node (ref "D34L1") (pin "KK") (pinfunction "31_KK") (pintype "bidirectional"))
      (node (ref "D34L1") (pin "M") (pinfunction "11_M") (pintype "bidirectional"))
      (node (ref "D34L1") (pin "MM") (pinfunction "33_MM") (pintype "bidirectional"))
      (node (ref "D34L1") (pin "P") (pinfunction "13_P") (pintype "bidirectional"))
      (node (ref "D34L1") (pin "PP") (pinfunction "35_PP") (pintype "bidirectional"))
      (node (ref "D34L1") (pin "S") (pinfunction "15_S") (pintype "bidirectional"))
      (node (ref "D34L1") (pin "SS") (pinfunction "37_SS") (pintype "bidirectional"))
      (node (ref "D34L1") (pin "U") (pinfunction "17_U") (pintype "bidirectional"))
      (node (ref "D34L1") (pin "UU") (pinfunction "39_UU") (pintype "bidirectional"))
      (node (ref "D34L1") (pin "W") (pinfunction "19_W") (pintype "bidirectional"))
      (node (ref "D34L1") (pin "Y") (pinfunction "21_Y") (pintype "bidirectional"))
      (node (ref "D34L2") (pin "A") (pinfunction "1_A") (pintype "bidirectional"))
      (node (ref "D34L2") (pin "AA") (pinfunction "23_AA") (pintype "bidirectional"))
      (node (ref "D34L2") (pin "C") (pinfunction "3_C") (pintype "bidirectional"))
      (node (ref "D34L2") (pin "CC") (pinfunction "25_CC") (pintype "bidirectional"))
      (node (ref "D34L2") (pin "E") (pinfunction "5_E") (pintype "bidirectional"))
      (node (ref "D34L2") (pin "EE") (pinfunction "27_EE") (pintype "bidirectional"))
      (node (ref "D34L2") (pin "H") (pinfunction "7_H") (pintype "bidirectional"))
      (node (ref "D34L2") (pin "HH") (pinfunction "29_HH") (pintype "bidirectional"))
      (node (ref "D34L2") (pin "K") (pinfunction "9_K") (pintype "bidirectional"))
      (node (ref "D34L2") (pin "KK") (pinfunction "31_KK") (pintype "bidirectional"))
      (node (ref "D34L2") (pin "M") (pinfunction "11_M") (pintype "bidirectional"))
      (node (ref "D34L2") (pin "MM") (pinfunction "33_MM") (pintype "bidirectional"))
      (node (ref "D34L2") (pin "P") (pinfunction "13_P") (pintype "bidirectional"))
      (node (ref "D34L2") (pin "PP") (pinfunction "35_PP") (pintype "bidirectional"))
      (node (ref "D34L2") (pin "S") (pinfunction "15_S") (pintype "bidirectional"))
      (node (ref "D34L2") (pin "SS") (pinfunction "37_SS") (pintype "bidirectional"))
      (node (ref "D34L2") (pin "U") (pinfunction "17_U") (pintype "bidirectional"))
      (node (ref "D34L2") (pin "UU") (pinfunction "39_UU") (pintype "bidirectional"))
      (node (ref "D34L2") (pin "W") (pinfunction "19_W") (pintype "bidirectional"))
      (node (ref "D34L2") (pin "Y") (pinfunction "21_Y") (pintype "bidirectional"))
      (node (ref "D35L1") (pin "A") (pinfunction "1_A") (pintype "bidirectional"))
      (node (ref "D35L1") (pin "AA") (pinfunction "23_AA") (pintype "bidirectional"))
      (node (ref "D35L1") (pin "C") (pinfunction "3_C") (pintype "bidirectional"))
      (node (ref "D35L1") (pin "CC") (pinfunction "25_CC") (pintype "bidirectional"))
      (node (ref "D35L1") (pin "E") (pinfunction "5_E") (pintype "bidirectional"))
      (node (ref "D35L1") (pin "EE") (pinfunction "27_EE") (pintype "bidirectional"))
      (node (ref "D35L1") (pin "H") (pinfunction "7_H") (pintype "bidirectional"))
      (node (ref "D35L1") (pin "HH") (pinfunction "29_HH") (pintype "bidirectional"))
      (node (ref "D35L1") (pin "K") (pinfunction "9_K") (pintype "bidirectional"))
      (node (ref "D35L1") (pin "KK") (pinfunction "31_KK") (pintype "bidirectional"))
      (node (ref "D35L1") (pin "M") (pinfunction "11_M") (pintype "bidirectional"))
      (node (ref "D35L1") (pin "MM") (pinfunction "33_MM") (pintype "bidirectional"))
      (node (ref "D35L1") (pin "P") (pinfunction "13_P") (pintype "bidirectional"))
      (node (ref "D35L1") (pin "PP") (pinfunction "35_PP") (pintype "bidirectional"))
      (node (ref "D35L1") (pin "S") (pinfunction "15_S") (pintype "bidirectional"))
      (node (ref "D35L1") (pin "SS") (pinfunction "37_SS") (pintype "bidirectional"))
      (node (ref "D35L1") (pin "U") (pinfunction "17_U") (pintype "bidirectional"))
      (node (ref "D35L1") (pin "UU") (pinfunction "39_UU") (pintype "bidirectional"))
      (node (ref "D35L1") (pin "W") (pinfunction "19_W") (pintype "bidirectional"))
      (node (ref "D35L1") (pin "Y") (pinfunction "21_Y") (pintype "bidirectional"))
      (node (ref "D35L2") (pin "A") (pinfunction "1_A") (pintype "bidirectional"))
      (node (ref "D35L2") (pin "AA") (pinfunction "23_AA") (pintype "bidirectional"))
      (node (ref "D35L2") (pin "C") (pinfunction "3_C") (pintype "bidirectional"))
      (node (ref "D35L2") (pin "CC") (pinfunction "25_CC") (pintype "bidirectional"))
      (node (ref "D35L2") (pin "E") (pinfunction "5_E") (pintype "bidirectional"))
      (node (ref "D35L2") (pin "EE") (pinfunction "27_EE") (pintype "bidirectional"))
      (node (ref "D35L2") (pin "H") (pinfunction "7_H") (pintype "bidirectional"))
      (node (ref "D35L2") (pin "HH") (pinfunction "29_HH") (pintype "bidirectional"))
      (node (ref "D35L2") (pin "K") (pinfunction "9_K") (pintype "bidirectional"))
      (node (ref "D35L2") (pin "KK") (pinfunction "31_KK") (pintype "bidirectional"))
      (node (ref "D35L2") (pin "M") (pinfunction "11_M") (pintype "bidirectional"))
      (node (ref "D35L2") (pin "MM") (pinfunction "33_MM") (pintype "bidirectional"))
      (node (ref "D35L2") (pin "P") (pinfunction "13_P") (pintype "bidirectional"))
      (node (ref "D35L2") (pin "PP") (pinfunction "35_PP") (pintype "bidirectional"))
      (node (ref "D35L2") (pin "S") (pinfunction "15_S") (pintype "bidirectional"))
      (node (ref "D35L2") (pin "SS") (pinfunction "37_SS") (pintype "bidirectional"))
      (node (ref "D35L2") (pin "U") (pinfunction "17_U") (pintype "bidirectional"))
      (node (ref "D35L2") (pin "UU") (pinfunction "39_UU") (pintype "bidirectional"))
      (node (ref "D35L2") (pin "W") (pinfunction "19_W") (pintype "bidirectional"))
      (node (ref "D35L2") (pin "Y") (pinfunction "21_Y") (pintype "bidirectional"))
      (node (ref "D36L1") (pin "A") (pinfunction "1_A") (pintype "bidirectional"))
      (node (ref "D36L1") (pin "AA") (pinfunction "23_AA") (pintype "bidirectional"))
      (node (ref "D36L1") (pin "C") (pinfunction "3_C") (pintype "bidirectional"))
      (node (ref "D36L1") (pin "CC") (pinfunction "25_CC") (pintype "bidirectional"))
      (node (ref "D36L1") (pin "E") (pinfunction "5_E") (pintype "bidirectional"))
      (node (ref "D36L1") (pin "EE") (pinfunction "27_EE") (pintype "bidirectional"))
      (node (ref "D36L1") (pin "H") (pinfunction "7_H") (pintype "bidirectional"))
      (node (ref "D36L1") (pin "HH") (pinfunction "29_HH") (pintype "bidirectional"))
      (node (ref "D36L1") (pin "K") (pinfunction "9_K") (pintype "bidirectional"))
      (node (ref "D36L1") (pin "KK") (pinfunction "31_KK") (pintype "bidirectional"))
      (node (ref "D36L1") (pin "M") (pinfunction "11_M") (pintype "bidirectional"))
      (node (ref "D36L1") (pin "MM") (pinfunction "33_MM") (pintype "bidirectional"))
      (node (ref "D36L1") (pin "P") (pinfunction "13_P") (pintype "bidirectional"))
      (node (ref "D36L1") (pin "PP") (pinfunction "35_PP") (pintype "bidirectional"))
      (node (ref "D36L1") (pin "S") (pinfunction "15_S") (pintype "bidirectional"))
      (node (ref "D36L1") (pin "SS") (pinfunction "37_SS") (pintype "bidirectional"))
      (node (ref "D36L1") (pin "U") (pinfunction "17_U") (pintype "bidirectional"))
      (node (ref "D36L1") (pin "UU") (pinfunction "39_UU") (pintype "bidirectional"))
      (node (ref "D36L1") (pin "W") (pinfunction "19_W") (pintype "bidirectional"))
      (node (ref "D36L1") (pin "Y") (pinfunction "21_Y") (pintype "bidirectional"))
      (node (ref "D36L2") (pin "A") (pinfunction "1_A") (pintype "bidirectional"))
      (node (ref "D36L2") (pin "AA") (pinfunction "23_AA") (pintype "bidirectional"))
      (node (ref "D36L2") (pin "C") (pinfunction "3_C") (pintype "bidirectional"))
      (node (ref "D36L2") (pin "CC") (pinfunction "25_CC") (pintype "bidirectional"))
      (node (ref "D36L2") (pin "E") (pinfunction "5_E") (pintype "bidirectional"))
      (node (ref "D36L2") (pin "EE") (pinfunction "27_EE") (pintype "bidirectional"))
      (node (ref "D36L2") (pin "H") (pinfunction "7_H") (pintype "bidirectional"))
      (node (ref "D36L2") (pin "HH") (pinfunction "29_HH") (pintype "bidirectional"))
      (node (ref "D36L2") (pin "K") (pinfunction "9_K") (pintype "bidirectional"))
      (node (ref "D36L2") (pin "KK") (pinfunction "31_KK") (pintype "bidirectional"))
      (node (ref "D36L2") (pin "M") (pinfunction "11_M") (pintype "bidirectional"))
      (node (ref "D36L2") (pin "MM") (pinfunction "33_MM") (pintype "bidirectional"))
      (node (ref "D36L2") (pin "P") (pinfunction "13_P") (pintype "bidirectional"))
      (node (ref "D36L2") (pin "PP") (pinfunction "35_PP") (pintype "bidirectional"))
      (node (ref "D36L2") (pin "S") (pinfunction "15_S") (pintype "bidirectional"))
      (node (ref "D36L2") (pin "SS") (pinfunction "37_SS") (pintype "bidirectional"))
      (node (ref "D36L2") (pin "U") (pinfunction "17_U") (pintype "bidirectional"))
      (node (ref "D36L2") (pin "UU") (pinfunction "39_UU") (pintype "bidirectional"))
      (node (ref "D36L2") (pin "W") (pinfunction "19_W") (pintype "bidirectional"))
      (node (ref "D36L2") (pin "Y") (pinfunction "21_Y") (pintype "bidirectional"))
      (node (ref "DRIVE") (pin "A") (pinfunction "1_A") (pintype "bidirectional"))
      (node (ref "DRIVE") (pin "AA") (pinfunction "23_AA") (pintype "bidirectional"))
      (node (ref "DRIVE") (pin "B") (pinfunction "2_B") (pintype "bidirectional"))
      (node (ref "DRIVE") (pin "C") (pinfunction "3_C") (pintype "bidirectional"))
      (node (ref "DRIVE") (pin "CC") (pinfunction "25_CC") (pintype "bidirectional"))
      (node (ref "DRIVE") (pin "DD") (pinfunction "26_DD") (pintype "bidirectional"))
      (node (ref "DRIVE") (pin "E") (pinfunction "5_E") (pintype "bidirectional"))
      (node (ref "DRIVE") (pin "EE") (pinfunction "27_EE") (pintype "bidirectional"))
      (node (ref "DRIVE") (pin "F") (pinfunction "6_F") (pintype "bidirectional"))
      (node (ref "DRIVE") (pin "H") (pinfunction "7_H") (pintype "bidirectional"))
      (node (ref "DRIVE") (pin "HH") (pinfunction "29_HH") (pintype "bidirectional"))
      (node (ref "DRIVE") (pin "JJ") (pinfunction "30_JJ") (pintype "bidirectional"))
      (node (ref "DRIVE") (pin "K") (pinfunction "9_K") (pintype "bidirectional"))
      (node (ref "DRIVE") (pin "KK") (pinfunction "31_KK") (pintype "bidirectional"))
      (node (ref "DRIVE") (pin "L") (pinfunction "10_L") (pintype "bidirectional"))
      (node (ref "DRIVE") (pin "M") (pinfunction "11_M") (pintype "bidirectional"))
      (node (ref "DRIVE") (pin "MM") (pinfunction "33_MM") (pintype "bidirectional"))
      (node (ref "DRIVE") (pin "NN") (pinfunction "34_NN") (pintype "bidirectional"))
      (node (ref "DRIVE") (pin "P") (pinfunction "13_P") (pintype "bidirectional"))
      (node (ref "DRIVE") (pin "PP") (pinfunction "35_PP") (pintype "bidirectional"))
      (node (ref "DRIVE") (pin "R") (pinfunction "14_R") (pintype "bidirectional"))
      (node (ref "DRIVE") (pin "S") (pinfunction "15_S") (pintype "bidirectional"))
      (node (ref "DRIVE") (pin "SS") (pinfunction "37_SS") (pintype "bidirectional"))
      (node (ref "DRIVE") (pin "TT") (pinfunction "38_TT") (pintype "bidirectional"))
      (node (ref "DRIVE") (pin "U") (pinfunction "17_U") (pintype "bidirectional"))
      (node (ref "DRIVE") (pin "UU") (pinfunction "39_UU") (pintype "bidirectional"))
      (node (ref "DRIVE") (pin "V") (pinfunction "18_V") (pintype "bidirectional"))
      (node (ref "DRIVE") (pin "VV") (pinfunction "40_VV") (pintype "bidirectional"))
      (node (ref "DRIVE") (pin "W") (pinfunction "19_W") (pintype "bidirectional"))
      (node (ref "DRIVE") (pin "Y") (pinfunction "21_Y") (pintype "bidirectional"))
      (node (ref "DRIVE") (pin "Z") (pinfunction "22_Z") (pintype "bidirectional"))
      (node (ref "E1") (pin "4") (pinfunction "I1_4") (pintype "input"))
      (node (ref "E1") (pin "5") (pinfunction "I2_5") (pintype "input"))
      (node (ref "E11") (pin "5") (pinfunction "G2B_5") (pintype "input"))
      (node (ref "E12") (pin "5") (pinfunction "G2B_5") (pintype "input"))
      (node (ref "E13") (pin "5") (pinfunction "G2B_5") (pintype "input"))
      (node (ref "E2") (pin "2") (pinfunction "D_2") (pintype "input"))
      (node (ref "E4") (pin "6") (pinfunction "D_6") (pintype "input"))
      (node (ref "R10") (pin "1") (pinfunction "1_1") (pintype "passive"))
      (node (ref "R11") (pin "1") (pinfunction "1_1") (pintype "passive"))
      (node (ref "R12") (pin "1") (pinfunction "1_1") (pintype "passive"))
      (node (ref "R13") (pin "1") (pinfunction "1_1") (pintype "passive"))
      (node (ref "R14") (pin "1") (pinfunction "1_1") (pintype "passive"))
      (node (ref "R15") (pin "1") (pinfunction "1_1") (pintype "passive"))
      (node (ref "R16") (pin "1") (pinfunction "1_1") (pintype "passive"))
      (node (ref "R17") (pin "1") (pinfunction "1_1") (pintype "passive"))
    )
    (net (code "40") (name "INIT") (class "Default")
      (node (ref "E1") (pin "8") (pinfunction "O_8") (pintype "output"))
      (node (ref "E15") (pin "4") (pinfunction "I0_4") (pintype "input"))
      (node (ref "E15") (pin "5") (pinfunction "I1_5") (pintype "input"))
      (node (ref "E18") (pin "12") (pinfunction "I1_12") (pintype "input"))
      (node (ref "E37") (pin "1") (pinfunction "I0_1") (pintype "input"))
      (node (ref "E37") (pin "2") (pinfunction "I1_2") (pintype "input"))
    )
    (net (code "41") (name "MAINT") (class "Default")
      (node (ref "E16") (pin "9") (pinfunction "Q_9") (pintype "output"))
      (node (ref "E32") (pin "9") (pinfunction "I0_9") (pintype "input"))
      (node (ref "E35") (pin "3") (pinfunction "I1_3") (pintype "input"))
      (node (ref "E35") (pin "6") (pinfunction "I1_6") (pintype "input"))
      (node (ref "E35") (pin "9") (pinfunction "I1_9") (pintype "input"))
      (node (ref "E36") (pin "2") (pinfunction "I0_2") (pintype "input"))
      (node (ref "E36") (pin "6") (pinfunction "I1_6") (pintype "input"))
      (node (ref "E36") (pin "9") (pinfunction "I1_9") (pintype "input"))
    )
    (net (code "42") (name "MSB8") (class "Default")
      (node (ref "E21") (pin "12") (pinfunction "QD_12") (pintype "output"))
      (node (ref "E23") (pin "2") (pinfunction "J_2") (pintype "input"))
      (node (ref "E23") (pin "3") (pinfunction "K_3") (pintype "input"))
      (node (ref "E27") (pin "1") (pinfunction "I0_1") (pintype "input"))
      (node (ref "E8") (pin "5") (pinfunction "I2_5") (pintype "input"))
    )
    (net (code "43") (name "MSB12") (class "Default")
      (node (ref "E23") (pin "12") (pinfunction "QD_12") (pintype "output"))
      (node (ref "E29") (pin "1") (pinfunction "I0_1") (pintype "input"))
      (node (ref "E8") (pin "2") (pinfunction "I1_2") (pintype "input"))
    )
    (net (code "44") (name "Net-(70-P)") (class "Default")
      (node (ref "70") (pin "1") (pinfunction "P_1") (pintype "passive"))
      (node (ref "E14") (pin "15") (pinfunction "Y0_15") (pintype "output"))
    )
    (net (code "45") (name "Net-(71-P)") (class "Default")
      (node (ref "71") (pin "1") (pinfunction "P_1") (pintype "passive"))
      (node (ref "E14") (pin "14") (pinfunction "Y1_14") (pintype "output"))
    )
    (net (code "46") (name "Net-(72-P)") (class "Default")
      (node (ref "72") (pin "1") (pinfunction "P_1") (pintype "passive"))
      (node (ref "E14") (pin "13") (pinfunction "Y2_13") (pintype "output"))
    )
    (net (code "47") (name "Net-(73-P)") (class "Default")
      (node (ref "73") (pin "1") (pinfunction "P_1") (pintype "passive"))
      (node (ref "E14") (pin "12") (pinfunction "Y3_12") (pintype "output"))
    )
    (net (code "48") (name "Net-(74-P)") (class "Default")
      (node (ref "74") (pin "1") (pinfunction "P_1") (pintype "passive"))
      (node (ref "E14") (pin "11") (pinfunction "Y4_11") (pintype "output"))
    )
    (net (code "49") (name "Net-(75-P)") (class "Default")
      (node (ref "75") (pin "1") (pinfunction "P_1") (pintype "passive"))
      (node (ref "E14") (pin "10") (pinfunction "Y5_10") (pintype "output"))
    )
    (net (code "50") (name "Net-(76-P)") (class "Default")
      (node (ref "76") (pin "1") (pinfunction "P_1") (pintype "passive"))
      (node (ref "E14") (pin "9") (pinfunction "Y6_9") (pintype "output"))
    )
    (net (code "51") (name "Net-(77-P)") (class "Default")
      (node (ref "77") (pin "1") (pinfunction "P_1") (pintype "passive"))
      (node (ref "E14") (pin "7") (pinfunction "Y7_7") (pintype "output"))
    )
    (net (code "52") (name "Net-(E1B-O)") (class "Default")
      (node (ref "E1") (pin "10") (pinfunction "I1_10") (pintype "input"))
      (node (ref "E1") (pin "6") (pinfunction "O_6") (pintype "output"))
      (node (ref "E1") (pin "9") (pinfunction "I0_9") (pintype "input"))
    )
    (net (code "53") (name "Net-(E1C-I2)") (class "Default")
      (node (ref "E1") (pin "11") (pinfunction "I2_11") (pintype "input"))
      (node (ref "E2") (pin "6") (pinfunction "~{Q}_6") (pintype "output"))
    )
    (net (code "54") (name "Net-(E4A-A)") (class "Default")
      (node (ref "E4") (pin "10") (pinfunction "ENT_10") (pintype "input"))
      (node (ref "E4") (pin "3") (pinfunction "A_3") (pintype "input"))
      (node (ref "E4") (pin "4") (pinfunction "B_4") (pintype "input"))
      (node (ref "E4") (pin "7") (pinfunction "ENP_7") (pintype "input"))
      (node (ref "R19") (pin "2") (pinfunction "2_2") (pintype "passive"))
    )
    (net (code "55") (name "Net-(E4A-C)") (class "Default")
      (node (ref "E4") (pin "5") (pinfunction "C_5") (pintype "input"))
      (node (ref "E5") (pin "3") (pinfunction "O_3") (pintype "output"))
    )
    (net (code "56") (name "Net-(E5A-I0)") (class "Default")
      (node (ref "E5") (pin "1") (pinfunction "I0_1") (pintype "input"))
      (node (ref "E5") (pin "11") (pinfunction "O_11") (pintype "output"))
    )
    (net (code "57") (name "Net-(E8A-O)") (class "Default")
      (node (ref "E8") (pin "11") (pinfunction "I2_11") (pintype "input"))
      (node (ref "E8") (pin "12") (pinfunction "O_12") (pintype "output"))
    )
    (net (code "58") (name "Net-(E8B-O)") (class "Default")
      (node (ref "E8") (pin "6") (pinfunction "O_6") (pintype "output"))
      (node (ref "E8") (pin "9") (pinfunction "I0_9") (pintype "input"))
    )
    (net (code "59") (name "Net-(E10A-I0)") (class "Default")
      (node (ref "E10") (pin "1") (pinfunction "I0_1") (pintype "input"))
      (node (ref "E10") (pin "6") (pinfunction "O_6") (pintype "output"))
    )
    (net (code "60") (name "Net-(E10A-O)") (class "Default")
      (node (ref "E10") (pin "10") (pinfunction "I1_10") (pintype "input"))
      (node (ref "E10") (pin "11") (pinfunction "I2_11") (pintype "input"))
      (node (ref "E10") (pin "12") (pinfunction "O_12") (pintype "output"))
    )
    (net (code "61") (name "Net-(E10C-O)") (class "Default")
      (node (ref "E10") (pin "8") (pinfunction "O_8") (pintype "output"))
      (node (ref "E37") (pin "12") (pinfunction "I0_12") (pintype "input"))
      (node (ref "E37") (pin "13") (pinfunction "I1_13") (pintype "input"))
    )
    (net (code "62") (name "Net-(E14A-G2A)") (class "Default")
      (node (ref "E1") (pin "12") (pinfunction "O_12") (pintype "output"))
      (node (ref "E14") (pin "4") (pinfunction "G2A_4") (pintype "input"))
      (node (ref "E14") (pin "5") (pinfunction "G2B_5") (pintype "input"))
    )
    (net (code "63") (name "Net-(E15A-O)") (class "Default")
      (node (ref "E15") (pin "3") (pinfunction "O_3") (pintype "output"))
      (node (ref "E8") (pin "13") (pinfunction "I2_13") (pintype "input"))
      (node (ref "E8") (pin "3") (pinfunction "I0_3") (pintype "input"))
    )
    (net (code "64") (name "Net-(E15C-I0)") (class "Default")
      (node (ref "E15") (pin "9") (pinfunction "I0_9") (pintype "input"))
      (node (ref "E20") (pin "11") (pinfunction "O_11") (pintype "output"))
      (node (ref "E24") (pin "10") (pinfunction "I1_10") (pintype "input"))
    )
    (net (code "65") (name "Net-(E15C-O)") (class "Default")
      (node (ref "E15") (pin "8") (pinfunction "O_8") (pintype "output"))
      (node (ref "E24") (pin "12") (pinfunction "I0_12") (pintype "input"))
    )
    (net (code "66") (name "Net-(E15D-O)") (class "Default")
      (node (ref "E15") (pin "11") (pinfunction "O_11") (pintype "output"))
      (node (ref "E8") (pin "10") (pinfunction "I1_10") (pintype "input"))
    )
    (net (code "67") (name "Net-(E17A-CLK)") (class "Default")
      (node (ref "E17") (pin "1") (pinfunction "CLK_1") (pintype "input"))
      (node (ref "E26") (pin "8") (pinfunction "O_8") (pintype "output"))
    )
    (net (code "68") (name "Net-(E17A-~{Q})") (class "Default")
      (node (ref "E17") (pin "14") (pinfunction "~{Q}_14") (pintype "output"))
      (node (ref "E18") (pin "9") (pinfunction "I1_9") (pintype "input"))
    )
    (net (code "69") (name "Net-(E17B-CLR)") (class "Default")
      (node (ref "E17") (pin "8") (pinfunction "CLR_8") (pintype "input"))
      (node (ref "E18") (pin "13") (pinfunction "O_13") (pintype "output"))
    )
    (net (code "70") (name "Net-(E17B-J)") (class "Default")
      (node (ref "E17") (pin "12") (pinfunction "K_12") (pintype "input"))
      (node (ref "E17") (pin "9") (pinfunction "J_9") (pintype "input"))
      (node (ref "E37") (pin "5") (pinfunction "I1_5") (pintype "input"))
      (node (ref "E8") (pin "8") (pinfunction "O_8") (pintype "output"))
    )
    (net (code "71") (name "Net-(E18A-I1)") (class "Default")
      (node (ref "E18") (pin "3") (pinfunction "I1_3") (pintype "input"))
      (node (ref "E19") (pin "14") (pinfunction "~{Q}_14") (pintype "output"))
    )
    (net (code "72") (name "Net-(E18B-I1)") (class "Default")
      (node (ref "E18") (pin "6") (pinfunction "I1_6") (pintype "input"))
      (node (ref "E19") (pin "10") (pinfunction "~{Q}_10") (pintype "output"))
    )
    (net (code "73") (name "Net-(E19A-CLK)") (class "Default")
      (node (ref "E19") (pin "1") (pinfunction "CLK_1") (pintype "input"))
      (node (ref "E26") (pin "3") (pinfunction "O_3") (pintype "output"))
    )
    (net (code "74") (name "Net-(E19B-CLK)") (class "Default")
      (node (ref "E19") (pin "6") (pinfunction "CLK_6") (pintype "input"))
      (node (ref "E26") (pin "6") (pinfunction "O_6") (pintype "output"))
    )
    (net (code "75") (name "Net-(E20A-I1)") (class "Default")
      (node (ref "E20") (pin "2") (pinfunction "I1_2") (pintype "input"))
      (node (ref "E20") (pin "6") (pinfunction "O_6") (pintype "output"))
    )
    (net (code "76") (name "Net-(E20A-O)") (class "Default")
      (node (ref "E20") (pin "3") (pinfunction "O_3") (pintype "output"))
      (node (ref "E33") (pin "10") (pinfunction "I1_10") (pintype "input"))
      (node (ref "E33") (pin "9") (pinfunction "I0_9") (pintype "input"))
    )
    (net (code "77") (name "Net-(E21A-J)") (class "Default")
      (node (ref "E21") (pin "2") (pinfunction "J_2") (pintype "input"))
      (node (ref "E21") (pin "3") (pinfunction "K_3") (pintype "input"))
      (node (ref "E22") (pin "12") (pinfunction "QD_12") (pintype "output"))
      (node (ref "E28") (pin "1") (pinfunction "I0_1") (pintype "input"))
    )
    (net (code "78") (name "Net-(E21A-QA)") (class "Default")
      (node (ref "E21") (pin "15") (pinfunction "QA_15") (pintype "output"))
      (node (ref "E27") (pin "12") (pinfunction "I0_12") (pintype "input"))
    )
    (net (code "79") (name "Net-(E21A-QB)") (class "Default")
      (node (ref "E21") (pin "14") (pinfunction "QB_14") (pintype "output"))
      (node (ref "E27") (pin "9") (pinfunction "I0_9") (pintype "input"))
    )
    (net (code "80") (name "Net-(E21A-QC)") (class "Default")
      (node (ref "E21") (pin "13") (pinfunction "QC_13") (pintype "output"))
      (node (ref "E27") (pin "4") (pinfunction "I0_4") (pintype "input"))
    )
    (net (code "81") (name "Net-(E22A-QA)") (class "Default")
      (node (ref "E22") (pin "15") (pinfunction "QA_15") (pintype "output"))
      (node (ref "E28") (pin "12") (pinfunction "I0_12") (pintype "input"))
    )
    (net (code "82") (name "Net-(E22A-QB)") (class "Default")
      (node (ref "E22") (pin "14") (pinfunction "QB_14") (pintype "output"))
      (node (ref "E28") (pin "9") (pinfunction "I0_9") (pintype "input"))
    )
    (net (code "83") (name "Net-(E22A-QC)") (class "Default")
      (node (ref "E22") (pin "13") (pinfunction "QC_13") (pintype "output"))
      (node (ref "E28") (pin "4") (pinfunction "I0_4") (pintype "input"))
    )
    (net (code "84") (name "Net-(E23A-QA)") (class "Default")
      (node (ref "E23") (pin "15") (pinfunction "QA_15") (pintype "output"))
      (node (ref "E29") (pin "12") (pinfunction "I0_12") (pintype "input"))
    )
    (net (code "85") (name "Net-(E23A-QB)") (class "Default")
      (node (ref "E23") (pin "14") (pinfunction "QB_14") (pintype "output"))
      (node (ref "E29") (pin "9") (pinfunction "I0_9") (pintype "input"))
    )
    (net (code "86") (name "Net-(E23A-QC)") (class "Default")
      (node (ref "E23") (pin "13") (pinfunction "QC_13") (pintype "output"))
      (node (ref "E29") (pin "4") (pinfunction "I0_4") (pintype "input"))
    )
    (net (code "87") (name "Net-(E24A-I1)") (class "Default")
      (node (ref "E24") (pin "2") (pinfunction "I1_2") (pintype "input"))
      (node (ref "E27") (pin "10") (pinfunction "I1_10") (pintype "input"))
      (node (ref "E27") (pin "13") (pinfunction "I1_13") (pintype "input"))
      (node (ref "E27") (pin "2") (pinfunction "I1_2") (pintype "input"))
      (node (ref "E27") (pin "5") (pinfunction "I1_5") (pintype "input"))
      (node (ref "E28") (pin "10") (pinfunction "I1_10") (pintype "input"))
      (node (ref "E28") (pin "13") (pinfunction "I1_13") (pintype "input"))
      (node (ref "E28") (pin "2") (pinfunction "I1_2") (pintype "input"))
      (node (ref "E28") (pin "5") (pinfunction "I1_5") (pintype "input"))
      (node (ref "E35") (pin "13") (pinfunction "O_13") (pintype "output"))
    )
    (net (code "88") (name "Net-(E24A-O)") (class "Default")
      (node (ref "E24") (pin "3") (pinfunction "O_3") (pintype "output"))
      (node (ref "E29") (pin "10") (pinfunction "I1_10") (pintype "input"))
      (node (ref "E29") (pin "13") (pinfunction "I1_13") (pintype "input"))
      (node (ref "E29") (pin "2") (pinfunction "I1_2") (pintype "input"))
      (node (ref "E29") (pin "5") (pinfunction "I1_5") (pintype "input"))
    )
    (net (code "89") (name "Net-(E24B-O)") (class "Default")
      (node (ref "E24") (pin "6") (pinfunction "O_6") (pintype "output"))
      (node (ref "E32") (pin "1") (pinfunction "I0_1") (pintype "input"))
    )
    (net (code "90") (name "Net-(E24C-O)") (class "Default")
      (node (ref "E24") (pin "8") (pinfunction "O_8") (pintype "output"))
      (node (ref "E30") (pin "13") (pinfunction "CLR_13") (pintype "input"))
    )
    (net (code "91") (name "Net-(E25C-O)") (class "Default")
      (node (ref "E25") (pin "6") (pinfunction "O_6") (pintype "output"))
      (node (ref "E31") (pin "1") (pinfunction "I0_1") (pintype "input"))
      (node (ref "E31") (pin "2") (pinfunction "I1_2") (pintype "input"))
    )
    (net (code "92") (name "Net-(E25D-O)") (class "Default")
      (node (ref "E25") (pin "8") (pinfunction "O_8") (pintype "output"))
      (node (ref "E31") (pin "13") (pinfunction "I3_13") (pintype "input"))
    )
    (net (code "93") (name "Net-(E25E-O)") (class "Default")
      (node (ref "E25") (pin "10") (pinfunction "O_10") (pintype "output"))
      (node (ref "E26") (pin "12") (pinfunction "I0_12") (pintype "input"))
      (node (ref "E26") (pin "13") (pinfunction "I1_13") (pintype "input"))
    )
    (net (code "94") (name "Net-(E25F-O)") (class "Default")
      (node (ref "E25") (pin "12") (pinfunction "O_12") (pintype "output"))
      (node (ref "E36") (pin "11") (pinfunction "I0_11") (pintype "input"))
      (node (ref "E36") (pin "12") (pinfunction "I1_12") (pintype "input"))
    )
    (net (code "95") (name "Net-(E30A-Q)") (class "Default")
      (node (ref "E30") (pin "5") (pinfunction "Q_5") (pintype "output"))
      (node (ref "E33") (pin "2") (pinfunction "I1_2") (pintype "input"))
    )
    (net (code "96") (name "Net-(E30B-CLK)") (class "Default")
      (node (ref "E30") (pin "11") (pinfunction "CLK_11") (pintype "input"))
      (node (ref "E33") (pin "6") (pinfunction "O_6") (pintype "open_collector"))
      (node (ref "R18") (pin "1") (pinfunction "1_1") (pintype "passive"))
    )
    (net (code "97") (name "Net-(E31A-O)") (class "Default")
      (node (ref "E31") (pin "6") (pinfunction "O_6") (pintype "output"))
      (node (ref "E33") (pin "4") (pinfunction "I0_4") (pintype "input"))
    )
    (net (code "98") (name "Net-(E31B-O)") (class "Default")
      (node (ref "E31") (pin "8") (pinfunction "O_8") (pintype "output"))
      (node (ref "E33") (pin "5") (pinfunction "I1_5") (pintype "input"))
    )
    (net (code "99") (name "Net-(E32A-O)") (class "Default")
      (node (ref "E32") (pin "12") (pinfunction "O_12") (pintype "output"))
      (node (ref "E32") (pin "4") (pinfunction "I1_4") (pintype "input"))
      (node (ref "E32") (pin "5") (pinfunction "I2_5") (pintype "input"))
    )
    (net (code "100") (name "Net-(E32C-O)") (class "Default")
      (node (ref "E32") (pin "8") (pinfunction "O_8") (pintype "output"))
      (node (ref "E35") (pin "11") (pinfunction "I0_11") (pintype "input"))
    )
    (net (code "101") (name "Net-(PAD10-P)") (class "Default")
      (node (ref "E38") (pin "1") (pinfunction "1_1") (pintype "passive"))
      (node (ref "PAD10") (pin "1") (pinfunction "P_1") (pintype "passive"))
    )
    (net (code "102") (name "Net-(PAD11-P)") (class "Default")
      (node (ref "E38") (pin "2") (pinfunction "2_2") (pintype "passive"))
      (node (ref "PAD11") (pin "1") (pinfunction "P_1") (pintype "passive"))
    )
    (net (code "103") (name "Net-(PAD12-P)") (class "Default")
      (node (ref "E38") (pin "3") (pinfunction "3_3") (pintype "passive"))
      (node (ref "PAD12") (pin "1") (pinfunction "P_1") (pintype "passive"))
    )
    (net (code "104") (name "Net-(PAD13-P)") (class "Default")
      (node (ref "E38") (pin "4") (pinfunction "4_4") (pintype "passive"))
      (node (ref "PAD13") (pin "1") (pinfunction "P_1") (pintype "passive"))
    )
    (net (code "105") (name "Net-(PAD14-P)") (class "Default")
      (node (ref "E38") (pin "5") (pinfunction "5_5") (pintype "passive"))
      (node (ref "PAD14") (pin "1") (pinfunction "P_1") (pintype "passive"))
    )
    (net (code "106") (name "Net-(PAD15-P)") (class "Default")
      (node (ref "E38") (pin "6") (pinfunction "6_6") (pintype "passive"))
      (node (ref "PAD15") (pin "1") (pinfunction "P_1") (pintype "passive"))
    )
    (net (code "107") (name "Net-(PAD16-P)") (class "Default")
      (node (ref "E38") (pin "7") (pinfunction "7_7") (pintype "passive"))
      (node (ref "PAD16") (pin "1") (pinfunction "P_1") (pintype "passive"))
    )
    (net (code "108") (name "Net-(PAD17-P)") (class "Default")
      (node (ref "E38") (pin "8") (pinfunction "8_8") (pintype "passive"))
      (node (ref "PAD17") (pin "1") (pinfunction "P_1") (pintype "passive"))
    )
    (net (code "109") (name "Net-(PAD18-P)") (class "Default")
      (node (ref "E40") (pin "1") (pinfunction "1_1") (pintype "passive"))
      (node (ref "PAD18") (pin "1") (pinfunction "P_1") (pintype "passive"))
    )
    (net (code "110") (name "Net-(PAD19-P)") (class "Default")
      (node (ref "E40") (pin "2") (pinfunction "2_2") (pintype "passive"))
      (node (ref "PAD19") (pin "1") (pinfunction "P_1") (pintype "passive"))
    )
    (net (code "111") (name "Net-(PAD20-P)") (class "Default")
      (node (ref "E38") (pin "16") (pinfunction "16_16") (pintype "passive"))
      (node (ref "PAD20") (pin "1") (pinfunction "P_1") (pintype "passive"))
    )
    (net (code "112") (name "Net-(PAD21-P)") (class "Default")
      (node (ref "E38") (pin "15") (pinfunction "15_15") (pintype "passive"))
      (node (ref "PAD21") (pin "1") (pinfunction "P_1") (pintype "passive"))
    )
    (net (code "113") (name "Net-(PAD22-P)") (class "Default")
      (node (ref "E38") (pin "14") (pinfunction "14_14") (pintype "passive"))
      (node (ref "PAD22") (pin "1") (pinfunction "P_1") (pintype "passive"))
    )
    (net (code "114") (name "Net-(PAD23-P)") (class "Default")
      (node (ref "E38") (pin "13") (pinfunction "13_13") (pintype "passive"))
      (node (ref "PAD23") (pin "1") (pinfunction "P_1") (pintype "passive"))
    )
    (net (code "115") (name "Net-(PAD24-P)") (class "Default")
      (node (ref "E38") (pin "12") (pinfunction "12_12") (pintype "passive"))
      (node (ref "PAD24") (pin "1") (pinfunction "P_1") (pintype "passive"))
    )
    (net (code "116") (name "Net-(PAD25-P)") (class "Default")
      (node (ref "E38") (pin "11") (pinfunction "11_11") (pintype "passive"))
      (node (ref "PAD25") (pin "1") (pinfunction "P_1") (pintype "passive"))
    )
    (net (code "117") (name "Net-(PAD26-P)") (class "Default")
      (node (ref "E38") (pin "10") (pinfunction "10_10") (pintype "passive"))
      (node (ref "PAD26") (pin "1") (pinfunction "P_1") (pintype "passive"))
    )
    (net (code "118") (name "Net-(PAD27-P)") (class "Default")
      (node (ref "E38") (pin "9") (pinfunction "9_9") (pintype "passive"))
      (node (ref "PAD27") (pin "1") (pinfunction "P_1") (pintype "passive"))
    )
    (net (code "119") (name "Net-(PAD28-P)") (class "Default")
      (node (ref "E40") (pin "3") (pinfunction "3_3") (pintype "passive"))
      (node (ref "PAD28") (pin "1") (pinfunction "P_1") (pintype "passive"))
    )
    (net (code "120") (name "Net-(PAD29-P)") (class "Default")
      (node (ref "E40") (pin "4") (pinfunction "4_4") (pintype "passive"))
      (node (ref "PAD29") (pin "1") (pinfunction "P_1") (pintype "passive"))
    )
    (net (code "121") (name "Net-(PAD30-P)") (class "Default")
      (node (ref "E40") (pin "5") (pinfunction "5_5") (pintype "passive"))
      (node (ref "PAD30") (pin "1") (pinfunction "P_1") (pintype "passive"))
    )
    (net (code "122") (name "Net-(PAD31-P)") (class "Default")
      (node (ref "E40") (pin "6") (pinfunction "6_6") (pintype "passive"))
      (node (ref "PAD31") (pin "1") (pinfunction "P_1") (pintype "passive"))
    )
    (net (code "123") (name "Net-(PAD32-P)") (class "Default")
      (node (ref "E40") (pin "7") (pinfunction "7_7") (pintype "passive"))
      (node (ref "PAD32") (pin "1") (pinfunction "P_1") (pintype "passive"))
    )
    (net (code "124") (name "Net-(PAD33-P)") (class "Default")
      (node (ref "E40") (pin "8") (pinfunction "8_8") (pintype "passive"))
      (node (ref "PAD33") (pin "1") (pinfunction "P_1") (pintype "passive"))
    )
    (net (code "125") (name "Net-(PAD34-P)") (class "Default")
      (node (ref "E40") (pin "16") (pinfunction "16_16") (pintype "passive"))
      (node (ref "PAD34") (pin "1") (pinfunction "P_1") (pintype "passive"))
    )
    (net (code "126") (name "Net-(PAD35-P)") (class "Default")
      (node (ref "E40") (pin "15") (pinfunction "15_15") (pintype "passive"))
      (node (ref "PAD35") (pin "1") (pinfunction "P_1") (pintype "passive"))
    )
    (net (code "127") (name "Net-(PAD36-P)") (class "Default")
      (node (ref "E40") (pin "14") (pinfunction "14_14") (pintype "passive"))
      (node (ref "PAD36") (pin "1") (pinfunction "P_1") (pintype "passive"))
    )
    (net (code "128") (name "Net-(PAD37-P)") (class "Default")
      (node (ref "E40") (pin "13") (pinfunction "13_13") (pintype "passive"))
      (node (ref "PAD37") (pin "1") (pinfunction "P_1") (pintype "passive"))
    )
    (net (code "129") (name "Net-(PAD38-P)") (class "Default")
      (node (ref "E40") (pin "12") (pinfunction "12_12") (pintype "passive"))
      (node (ref "PAD38") (pin "1") (pinfunction "P_1") (pintype "passive"))
    )
    (net (code "130") (name "Net-(PAD39-P)") (class "Default")
      (node (ref "E40") (pin "11") (pinfunction "11_11") (pintype "passive"))
      (node (ref "PAD39") (pin "1") (pinfunction "P_1") (pintype "passive"))
    )
    (net (code "131") (name "Net-(PAD40-P)") (class "Default")
      (node (ref "E40") (pin "10") (pinfunction "10_10") (pintype "passive"))
      (node (ref "PAD40") (pin "1") (pinfunction "P_1") (pintype "passive"))
    )
    (net (code "132") (name "Net-(PAD41-P)") (class "Default")
      (node (ref "E40") (pin "9") (pinfunction "9_9") (pintype "passive"))
      (node (ref "PAD41") (pin "1") (pinfunction "P_1") (pintype "passive"))
    )
    (net (code "133") (name "Net-(PAD42-P)") (class "Default")
      (node (ref "E39") (pin "1") (pinfunction "1_1") (pintype "passive"))
      (node (ref "PAD42") (pin "1") (pinfunction "P_1") (pintype "passive"))
    )
    (net (code "134") (name "Net-(PAD43-P)") (class "Default")
      (node (ref "E39") (pin "2") (pinfunction "2_2") (pintype "passive"))
      (node (ref "PAD43") (pin "1") (pinfunction "P_1") (pintype "passive"))
    )
    (net (code "135") (name "Net-(PAD44-P)") (class "Default")
      (node (ref "E39") (pin "3") (pinfunction "3_3") (pintype "passive"))
      (node (ref "PAD44") (pin "1") (pinfunction "P_1") (pintype "passive"))
    )
    (net (code "136") (name "Net-(PAD45-P)") (class "Default")
      (node (ref "E39") (pin "4") (pinfunction "4_4") (pintype "passive"))
      (node (ref "PAD45") (pin "1") (pinfunction "P_1") (pintype "passive"))
    )
    (net (code "137") (name "Net-(PAD46-P)") (class "Default")
      (node (ref "E39") (pin "5") (pinfunction "5_5") (pintype "passive"))
      (node (ref "PAD46") (pin "1") (pinfunction "P_1") (pintype "passive"))
    )
    (net (code "138") (name "Net-(PAD47-P)") (class "Default")
      (node (ref "E39") (pin "6") (pinfunction "6_6") (pintype "passive"))
      (node (ref "PAD47") (pin "1") (pinfunction "P_1") (pintype "passive"))
    )
    (net (code "139") (name "Net-(PAD48-P)") (class "Default")
      (node (ref "E39") (pin "7") (pinfunction "7_7") (pintype "passive"))
      (node (ref "PAD48") (pin "1") (pinfunction "P_1") (pintype "passive"))
    )
    (net (code "140") (name "Net-(PAD49-P)") (class "Default")
      (node (ref "E39") (pin "8") (pinfunction "8_8") (pintype "passive"))
      (node (ref "PAD49") (pin "1") (pinfunction "P_1") (pintype "passive"))
    )
    (net (code "141") (name "Net-(PAD50-P)") (class "Default")
      (node (ref "E39") (pin "16") (pinfunction "16_16") (pintype "passive"))
      (node (ref "PAD50") (pin "1") (pinfunction "P_1") (pintype "passive"))
    )
    (net (code "142") (name "Net-(PAD51-P)") (class "Default")
      (node (ref "E39") (pin "15") (pinfunction "15_15") (pintype "passive"))
      (node (ref "PAD51") (pin "1") (pinfunction "P_1") (pintype "passive"))
    )
    (net (code "143") (name "Net-(PAD52-P)") (class "Default")
      (node (ref "E39") (pin "14") (pinfunction "14_14") (pintype "passive"))
      (node (ref "PAD52") (pin "1") (pinfunction "P_1") (pintype "passive"))
    )
    (net (code "144") (name "Net-(PAD53-P)") (class "Default")
      (node (ref "E39") (pin "13") (pinfunction "13_13") (pintype "passive"))
      (node (ref "PAD53") (pin "1") (pinfunction "P_1") (pintype "passive"))
    )
    (net (code "145") (name "Net-(PAD54-P)") (class "Default")
      (node (ref "E39") (pin "12") (pinfunction "12_12") (pintype "passive"))
      (node (ref "PAD54") (pin "1") (pinfunction "P_1") (pintype "passive"))
    )
    (net (code "146") (name "Net-(PAD55-P)") (class "Default")
      (node (ref "E39") (pin "11") (pinfunction "11_11") (pintype "passive"))
      (node (ref "PAD55") (pin "1") (pinfunction "P_1") (pintype "passive"))
    )
    (net (code "147") (name "Net-(PAD56-P)") (class "Default")
      (node (ref "E39") (pin "10") (pinfunction "10_10") (pintype "passive"))
      (node (ref "PAD56") (pin "1") (pinfunction "P_1") (pintype "passive"))
    )
    (net (code "148") (name "Net-(PAD57-P)") (class "Default")
      (node (ref "E39") (pin "9") (pinfunction "9_9") (pintype "passive"))
      (node (ref "PAD57") (pin "1") (pinfunction "P_1") (pintype "passive"))
    )
    (net (code "149") (name "PARITY") (class "Default")
      (node (ref "E15") (pin "1") (pinfunction "I0_1") (pintype "input"))
      (node (ref "E15") (pin "13") (pinfunction "I1_13") (pintype "input"))
      (node (ref "E15") (pin "2") (pinfunction "I1_2") (pintype "input"))
      (node (ref "E4") (pin "15") (pinfunction "RCO_15") (pintype "output"))
    )
    (net (code "150") (name "RD") (class "Default")
      (node (ref "E25") (pin "1") (pinfunction "I_1") (pintype "input"))
      (node (ref "E32") (pin "10") (pinfunction "I1_10") (pintype "input"))
      (node (ref "E35") (pin "10") (pinfunction "O_10") (pintype "output"))
    )
    (net (code "151") (name "RUN") (class "Default")
      (node (ref "E18") (pin "11") (pinfunction "I0_11") (pintype "input"))
      (node (ref "E30") (pin "9") (pinfunction "Q_9") (pintype "output"))
      (node (ref "E33") (pin "12") (pinfunction "I0_12") (pintype "input"))
      (node (ref "E33") (pin "13") (pinfunction "I1_13") (pintype "input"))
    )
    (net (code "152") (name "RX_DATA") (class "Default")
      (node (ref "E22") (pin "2") (pinfunction "J_2") (pintype "input"))
      (node (ref "E22") (pin "3") (pinfunction "K_3") (pintype "input"))
      (node (ref "E35") (pin "1") (pinfunction "O_1") (pintype "output"))
    )
    (net (code "153") (name "SHIFT") (class "Default")
      (node (ref "E32") (pin "3") (pinfunction "I0_3") (pintype "input"))
      (node (ref "E35") (pin "4") (pinfunction "O_4") (pintype "output"))
    )
    (net (code "154") (name "TR_SKIP") (class "Default")
      (node (ref "E18") (pin "1") (pinfunction "O_1") (pintype "output"))
      (node (ref "E19") (pin "16") (pinfunction "K_16") (pintype "input"))
      (node (ref "E20") (pin "1") (pinfunction "I0_1") (pintype "input"))
      (node (ref "E26") (pin "2") (pinfunction "I1_2") (pintype "input"))
    )
    (net (code "155") (name "VCC") (class "Default")
      (node (ref "C1") (pin "1") (pinfunction "1_1") (pintype "passive"))
      (node (ref "C10") (pin "1") (pinfunction "1_1") (pintype "passive"))
      (node (ref "C11") (pin "1") (pinfunction "1_1") (pintype "passive"))
      (node (ref "C12") (pin "1") (pinfunction "1_1") (pintype "passive"))
      (node (ref "C13") (pin "1") (pinfunction "1_1") (pintype "passive"))
      (node (ref "C14") (pin "1") (pinfunction "1_1") (pintype "passive"))
      (node (ref "C15") (pin "1") (pinfunction "1_1") (pintype "passive"))
      (node (ref "C16") (pin "1") (pinfunction "1_1") (pintype "passive"))
      (node (ref "C17") (pin "1") (pinfunction "1_1") (pintype "passive"))
      (node (ref "C18") (pin "1") (pinfunction "1_1") (pintype "passive"))
      (node (ref "C19") (pin "1") (pinfunction "1_1") (pintype "passive"))
      (node (ref "C2") (pin "1") (pinfunction "1_1") (pintype "passive"))
      (node (ref "C20") (pin "1") (pinfunction "1_1") (pintype "passive"))
      (node (ref "C21") (pin "1") (pinfunction "1_1") (pintype "passive"))
      (node (ref "C22") (pin "1") (pinfunction "1_1") (pintype "passive"))
      (node (ref "C23") (pin "1") (pinfunction "1_1") (pintype "passive"))
      (node (ref "C24") (pin "1") (pinfunction "1_1") (pintype "passive"))
      (node (ref "C25") (pin "1") (pinfunction "1_1") (pintype "passive"))
      (node (ref "C26") (pin "1") (pinfunction "1_1") (pintype "passive"))
      (node (ref "C27") (pin "1") (pinfunction "1_1") (pintype "passive"))
      (node (ref "C28") (pin "1") (pinfunction "1_1") (pintype "passive"))
      (node (ref "C29") (pin "1") (pinfunction "1_1") (pintype "passive"))
      (node (ref "C3") (pin "1") (pinfunction "1_1") (pintype "passive"))
      (node (ref "C30") (pin "1") (pinfunction "1_1") (pintype "passive"))
      (node (ref "C31") (pin "1") (pinfunction "1_1") (pintype "passive"))
      (node (ref "C32") (pin "1") (pinfunction "1_1") (pintype "passive"))
      (node (ref "C33") (pin "1") (pinfunction "1_1") (pintype "passive"))
      (node (ref "C34") (pin "1") (pinfunction "1_1") (pintype "passive"))
      (node (ref "C35") (pin "1") (pinfunction "1_1") (pintype "passive"))
      (node (ref "C36") (pin "1") (pinfunction "1_1") (pintype "passive"))
      (node (ref "C37") (pin "1") (pinfunction "1_1") (pintype "passive"))
      (node (ref "C38") (pin "1") (pinfunction "1_1") (pintype "passive"))
      (node (ref "C39") (pin "1") (pinfunction "1_1") (pintype "passive"))
      (node (ref "C4") (pin "1") (pinfunction "1_1") (pintype "passive"))
      (node (ref "C40") (pin "1") (pinfunction "1_1") (pintype "passive"))
      (node (ref "C41") (pin "1") (pinfunction "1_1") (pintype "passive"))
      (node (ref "C5") (pin "1") (pinfunction "1_1") (pintype "passive"))
      (node (ref "C6") (pin "1") (pinfunction "1_1") (pintype "passive"))
      (node (ref "C7") (pin "1") (pinfunction "1_1") (pintype "passive"))
      (node (ref "C8") (pin "1") (pinfunction "1_1") (pintype "passive"))
      (node (ref "C9") (pin "1") (pinfunction "1_1") (pintype "passive"))
      (node (ref "E14") (pin "6") (pinfunction "G1_6") (pintype "input"))
      (node (ref "E16") (pin "10") (pinfunction "PRE_10") (pintype "input"))
      (node (ref "E16") (pin "4") (pinfunction "PRE_4") (pintype "input"))
      (node (ref "E17") (pin "7") (pinfunction "PRE_7") (pintype "input"))
      (node (ref "E2") (pin "1") (pinfunction "CLR_1") (pintype "input"))
      (node (ref "E2") (pin "10") (pinfunction "PRE_10") (pintype "input"))
      (node (ref "E2") (pin "11") (pinfunction "CLK_11") (pintype "input"))
      (node (ref "E2") (pin "12") (pinfunction "D_12") (pintype "input"))
      (node (ref "E2") (pin "13") (pinfunction "CLR_13") (pintype "input"))
      (node (ref "E20") (pin "10") (pinfunction "I1_10") (pintype "input"))
      (node (ref "E20") (pin "9") (pinfunction "I0_9") (pintype "input"))
      (node (ref "E25") (pin "11") (pinfunction "I_11") (pintype "input"))
      (node (ref "E25") (pin "13") (pinfunction "I_13") (pintype "input"))
      (node (ref "E30") (pin "10") (pinfunction "PRE_10") (pintype "input"))
      (node (ref "E30") (pin "12") (pinfunction "D_12") (pintype "input"))
      (node (ref "E30") (pin "4") (pinfunction "PRE_4") (pintype "input"))
      (node (ref "R1") (pin "2") (pinfunction "2_2") (pintype "passive"))
      (node (ref "R18") (pin "2") (pinfunction "2_2") (pintype "passive"))
      (node (ref "R19") (pin "1") (pinfunction "1_1") (pintype "passive"))
      (node (ref "R2") (pin "2") (pinfunction "2_2") (pintype "passive"))
      (node (ref "R3") (pin "2") (pinfunction "2_2") (pintype "passive"))
      (node (ref "R4") (pin "2") (pinfunction "2_2") (pintype "passive"))
      (node (ref "R5") (pin "2") (pinfunction "2_2") (pintype "passive"))
      (node (ref "R6") (pin "2") (pinfunction "2_2") (pintype "passive"))
      (node (ref "R7") (pin "2") (pinfunction "2_2") (pintype "passive"))
      (node (ref "R8") (pin "2") (pinfunction "2_2") (pintype "passive"))
      (node (ref "R9") (pin "2") (pinfunction "2_2") (pintype "passive"))
    )
    (net (code "156") (name "WRT") (class "Default")
      (node (ref "E10") (pin "5") (pinfunction "I2_5") (pintype "input"))
      (node (ref "E15") (pin "10") (pinfunction "I1_10") (pintype "input"))
      (node (ref "E25") (pin "2") (pinfunction "O_2") (pintype "output"))
      (node (ref "E37") (pin "4") (pinfunction "I0_4") (pintype "input"))
    )
    (net (code "157") (name "XDR2") (class "Default")
      (node (ref "E10") (pin "2") (pinfunction "I1_2") (pintype "input"))
      (node (ref "E5") (pin "12") (pinfunction "I0_12") (pintype "input"))
      (node (ref "E5") (pin "8") (pinfunction "O_8") (pintype "output"))
    )
    (net (code "158") (name "XFER_REQ") (class "Default")
      (node (ref "E19") (pin "4") (pinfunction "J_4") (pintype "input"))
      (node (ref "E20") (pin "12") (pinfunction "I0_12") (pintype "input"))
      (node (ref "E26") (pin "1") (pinfunction "I0_1") (pintype "input"))
      (node (ref "E36") (pin "4") (pinfunction "O_4") (pintype "output"))
    )
    (net (code "159") (name "unconnected-(D34L1-2-PadB)") (class "Default")
      (node (ref "D34L1") (pin "B") (pinfunction "2_B") (pintype "bidirectional"))
    )
    (net (code "160") (name "unconnected-(D34L1-34-PadNN)") (class "Default")
      (node (ref "D34L1") (pin "NN") (pinfunction "34_NN") (pintype "bidirectional"))
    )
    (net (code "161") (name "unconnected-(D34L1-38-PadTT)") (class "Default")
      (node (ref "D34L1") (pin "TT") (pinfunction "38_TT") (pintype "bidirectional"))
    )
    (net (code "162") (name "unconnected-(D34L1-40-PadVV)") (class "Default")
      (node (ref "D34L1") (pin "VV") (pinfunction "40_VV") (pintype "bidirectional"))
    )
    (net (code "163") (name "unconnected-(D34L2-2-PadB)") (class "Default")
      (node (ref "D34L2") (pin "B") (pinfunction "2_B") (pintype "bidirectional"))
    )
    (net (code "164") (name "unconnected-(D34L2-34-PadNN)") (class "Default")
      (node (ref "D34L2") (pin "NN") (pinfunction "34_NN") (pintype "bidirectional"))
    )
    (net (code "165") (name "unconnected-(D34L2-38-PadTT)") (class "Default")
      (node (ref "D34L2") (pin "TT") (pinfunction "38_TT") (pintype "bidirectional"))
    )
    (net (code "166") (name "unconnected-(D34L2-40-PadVV)") (class "Default")
      (node (ref "D34L2") (pin "VV") (pinfunction "40_VV") (pintype "bidirectional"))
    )
    (net (code "167") (name "unconnected-(D35L1-2-PadB)") (class "Default")
      (node (ref "D35L1") (pin "B") (pinfunction "2_B") (pintype "bidirectional"))
    )
    (net (code "168") (name "unconnected-(D35L1-40-PadVV)") (class "Default")
      (node (ref "D35L1") (pin "VV") (pinfunction "40_VV") (pintype "bidirectional"))
    )
    (net (code "169") (name "unconnected-(D35L2-2-PadB)") (class "Default")
      (node (ref "D35L2") (pin "B") (pinfunction "2_B") (pintype "bidirectional"))
    )
    (net (code "170") (name "unconnected-(D35L2-40-PadVV)") (class "Default")
      (node (ref "D35L2") (pin "VV") (pinfunction "40_VV") (pintype "bidirectional"))
    )
    (net (code "171") (name "unconnected-(D36L1-2-PadB)") (class "Default")
      (node (ref "D36L1") (pin "B") (pinfunction "2_B") (pintype "bidirectional"))
    )
    (net (code "172") (name "unconnected-(D36L1-40-PadVV)") (class "Default")
      (node (ref "D36L1") (pin "VV") (pinfunction "40_VV") (pintype "bidirectional"))
    )
    (net (code "173") (name "unconnected-(D36L2-2-PadB)") (class "Default")
      (node (ref "D36L2") (pin "B") (pinfunction "2_B") (pintype "bidirectional"))
    )
    (net (code "174") (name "unconnected-(D36L2-40-PadVV)") (class "Default")
      (node (ref "D36L2") (pin "VV") (pinfunction "40_VV") (pintype "bidirectional"))
    )
    (net (code "175") (name "unconnected-(E2A-Q-Pad5)") (class "Default")
      (node (ref "E2") (pin "5") (pinfunction "Q_5") (pintype "output"))
    )
    (net (code "176") (name "unconnected-(E2B-Q-Pad9)") (class "Default")
      (node (ref "E2") (pin "9") (pinfunction "Q_9") (pintype "output"))
    )
    (net (code "177") (name "unconnected-(E2B-~{Q}-Pad8)") (class "Default")
      (node (ref "E2") (pin "8") (pinfunction "~{Q}_8") (pintype "output"))
    )
    (net (code "178") (name "unconnected-(E4A-QA-Pad14)") (class "Default")
      (node (ref "E4") (pin "14") (pinfunction "QA_14") (pintype "output"))
    )
    (net (code "179") (name "unconnected-(E4A-QB-Pad13)") (class "Default")
      (node (ref "E4") (pin "13") (pinfunction "QB_13") (pintype "output"))
    )
    (net (code "180") (name "unconnected-(E4A-QC-Pad12)") (class "Default")
      (node (ref "E4") (pin "12") (pinfunction "QC_12") (pintype "output"))
    )
    (net (code "181") (name "unconnected-(E4A-QD-Pad11)") (class "Default")
      (node (ref "E4") (pin "11") (pinfunction "QD_11") (pintype "output"))
    )
    (net (code "182") (name "unconnected-(E11A-Y0-Pad15)") (class "Default")
      (node (ref "E11") (pin "15") (pinfunction "Y0_15") (pintype "output"))
    )
    (net (code "183") (name "unconnected-(E11A-Y2-Pad13)") (class "Default")
      (node (ref "E11") (pin "13") (pinfunction "Y2_13") (pintype "output"))
    )
    (net (code "184") (name "unconnected-(E11A-Y3-Pad12)") (class "Default")
      (node (ref "E11") (pin "12") (pinfunction "Y3_12") (pintype "output"))
    )
    (net (code "185") (name "unconnected-(E11A-Y4-Pad11)") (class "Default")
      (node (ref "E11") (pin "11") (pinfunction "Y4_11") (pintype "output"))
    )
    (net (code "186") (name "unconnected-(E11A-Y5-Pad10)") (class "Default")
      (node (ref "E11") (pin "10") (pinfunction "Y5_10") (pintype "output"))
    )
    (net (code "187") (name "unconnected-(E11A-Y6-Pad9)") (class "Default")
      (node (ref "E11") (pin "9") (pinfunction "Y6_9") (pintype "output"))
    )
    (net (code "188") (name "unconnected-(E12A-Y0-Pad15)") (class "Default")
      (node (ref "E12") (pin "15") (pinfunction "Y0_15") (pintype "output"))
    )
    (net (code "189") (name "unconnected-(E12A-Y1-Pad14)") (class "Default")
      (node (ref "E12") (pin "14") (pinfunction "Y1_14") (pintype "output"))
    )
    (net (code "190") (name "unconnected-(E12A-Y4-Pad11)") (class "Default")
      (node (ref "E12") (pin "11") (pinfunction "Y4_11") (pintype "output"))
    )
    (net (code "191") (name "unconnected-(E12A-Y5-Pad10)") (class "Default")
      (node (ref "E12") (pin "10") (pinfunction "Y5_10") (pintype "output"))
    )
    (net (code "192") (name "unconnected-(E12A-Y6-Pad9)") (class "Default")
      (node (ref "E12") (pin "9") (pinfunction "Y6_9") (pintype "output"))
    )
    (net (code "193") (name "unconnected-(E12A-Y7-Pad7)") (class "Default")
      (node (ref "E12") (pin "7") (pinfunction "Y7_7") (pintype "output"))
    )
    (net (code "194") (name "unconnected-(E13A-Y0-Pad15)") (class "Default")
      (node (ref "E13") (pin "15") (pinfunction "Y0_15") (pintype "output"))
    )
    (net (code "195") (name "unconnected-(E13A-Y1-Pad14)") (class "Default")
      (node (ref "E13") (pin "14") (pinfunction "Y1_14") (pintype "output"))
    )
    (net (code "196") (name "unconnected-(E13A-Y2-Pad13)") (class "Default")
      (node (ref "E13") (pin "13") (pinfunction "Y2_13") (pintype "output"))
    )
    (net (code "197") (name "unconnected-(E13A-Y3-Pad12)") (class "Default")
      (node (ref "E13") (pin "12") (pinfunction "Y3_12") (pintype "output"))
    )
    (net (code "198") (name "unconnected-(E17B-Q-Pad11)") (class "Default")
      (node (ref "E17") (pin "11") (pinfunction "Q_11") (pintype "output"))
    )
    (net (code "199") (name "unconnected-(E19A-Q-Pad15)") (class "Default")
      (node (ref "E19") (pin "15") (pinfunction "Q_15") (pintype "output"))
    )
    (net (code "200") (name "unconnected-(E19B-Q-Pad11)") (class "Default")
      (node (ref "E19") (pin "11") (pinfunction "Q_11") (pintype "output"))
    )
    (net (code "201") (name "unconnected-(E20C-O-Pad8)") (class "Default")
      (node (ref "E20") (pin "8") (pinfunction "O_8") (pintype "output"))
    )
    (net (code "202") (name "unconnected-(E21A-~{QD}-Pad11)") (class "Default")
      (node (ref "E21") (pin "11") (pinfunction "~{QD}_11") (pintype "output"))
    )
    (net (code "203") (name "unconnected-(E22A-~{QD}-Pad11)") (class "Default")
      (node (ref "E22") (pin "11") (pinfunction "~{QD}_11") (pintype "output"))
    )
    (net (code "204") (name "unconnected-(E23A-~{QD}-Pad11)") (class "Default")
      (node (ref "E23") (pin "11") (pinfunction "~{QD}_11") (pintype "output"))
    )
    (net (code "205") (name "unconnected-(E26D-O-Pad11)") (class "Default")
      (node (ref "E26") (pin "11") (pinfunction "O_11") (pintype "output"))
    )
    (net (code "206") (name "unconnected-(E30A-~{Q}-Pad6)") (class "Default")
      (node (ref "E30") (pin "6") (pinfunction "~{Q}_6") (pintype "output"))
    )
    (net (code "207") (name "unconnected-(E30B-~{Q}-Pad8)") (class "Default")
      (node (ref "E30") (pin "8") (pinfunction "~{Q}_8") (pintype "output"))
    )
    (net (code "208") (name "unconnected-(E36D-O-Pad13)") (class "Default")
      (node (ref "E36") (pin "13") (pinfunction "O_13") (pintype "output"))
    )
    (net (code "209") (name "~{ACB00}") (class "Default")
      (node (ref "D34L1") (pin "D") (pinfunction "4_D") (pintype "bidirectional"))
      (node (ref "D34L2") (pin "D") (pinfunction "4_D") (pintype "bidirectional"))
      (node (ref "E29") (pin "3") (pinfunction "O_3") (pintype "open_collector"))
    )
    (net (code "210") (name "~{ACB01}") (class "Default")
      (node (ref "D34L1") (pin "J") (pinfunction "8_J") (pintype "bidirectional"))
      (node (ref "D34L2") (pin "J") (pinfunction "8_J") (pintype "bidirectional"))
      (node (ref "E29") (pin "6") (pinfunction "O_6") (pintype "open_collector"))
    )
    (net (code "211") (name "~{ACB02}") (class "Default")
      (node (ref "D34L1") (pin "N") (pinfunction "12_N") (pintype "bidirectional"))
      (node (ref "D34L2") (pin "N") (pinfunction "12_N") (pintype "bidirectional"))
      (node (ref "E29") (pin "8") (pinfunction "O_8") (pintype "open_collector"))
    )
    (net (code "212") (name "~{ACB03}") (class "Default")
      (node (ref "D34L1") (pin "T") (pinfunction "16_T") (pintype "bidirectional"))
      (node (ref "D34L2") (pin "T") (pinfunction "16_T") (pintype "bidirectional"))
      (node (ref "E29") (pin "11") (pinfunction "O_11") (pintype "open_collector"))
    )
    (net (code "213") (name "~{ACB04}") (class "Default")
      (node (ref "D34L1") (pin "X") (pinfunction "20_X") (pintype "bidirectional"))
      (node (ref "D34L2") (pin "X") (pinfunction "20_X") (pintype "bidirectional"))
      (node (ref "E27") (pin "3") (pinfunction "O_3") (pintype "open_collector"))
    )
    (net (code "214") (name "~{ACB05}") (class "Default")
      (node (ref "D34L1") (pin "BB") (pinfunction "24_BB") (pintype "bidirectional"))
      (node (ref "D34L2") (pin "BB") (pinfunction "24_BB") (pintype "bidirectional"))
      (node (ref "E27") (pin "6") (pinfunction "O_6") (pintype "open_collector"))
    )
    (net (code "215") (name "~{ACB06}") (class "Default")
      (node (ref "D34L1") (pin "FF") (pinfunction "28_FF") (pintype "bidirectional"))
      (node (ref "D34L2") (pin "FF") (pinfunction "28_FF") (pintype "bidirectional"))
      (node (ref "E27") (pin "8") (pinfunction "O_8") (pintype "open_collector"))
    )
    (net (code "216") (name "~{ACB07}") (class "Default")
      (node (ref "D34L1") (pin "LL") (pinfunction "32_LL") (pintype "bidirectional"))
      (node (ref "D34L2") (pin "LL") (pinfunction "32_LL") (pintype "bidirectional"))
      (node (ref "E27") (pin "11") (pinfunction "O_11") (pintype "open_collector"))
    )
    (net (code "217") (name "~{ACB08}") (class "Default")
      (node (ref "D34L1") (pin "RR") (pinfunction "36_RR") (pintype "bidirectional"))
      (node (ref "D34L2") (pin "RR") (pinfunction "36_RR") (pintype "bidirectional"))
      (node (ref "E28") (pin "3") (pinfunction "O_3") (pintype "open_collector"))
    )
    (net (code "218") (name "~{ACB09}") (class "Default")
      (node (ref "D34L1") (pin "F") (pinfunction "6_F") (pintype "bidirectional"))
      (node (ref "D34L2") (pin "F") (pinfunction "6_F") (pintype "bidirectional"))
      (node (ref "E28") (pin "6") (pinfunction "O_6") (pintype "open_collector"))
    )
    (net (code "219") (name "~{ACB10}") (class "Default")
      (node (ref "D34L1") (pin "L") (pinfunction "10_L") (pintype "bidirectional"))
      (node (ref "D34L2") (pin "L") (pinfunction "10_L") (pintype "bidirectional"))
      (node (ref "E28") (pin "8") (pinfunction "O_8") (pintype "open_collector"))
    )
    (net (code "220") (name "~{ACB11}") (class "Default")
      (node (ref "D34L1") (pin "R") (pinfunction "14_R") (pintype "bidirectional"))
      (node (ref "D34L2") (pin "R") (pinfunction "14_R") (pintype "bidirectional"))
      (node (ref "E28") (pin "11") (pinfunction "O_11") (pintype "open_collector"))
    )
    (net (code "221") (name "~{ACCLEAR}") (class "Default")
      (node (ref "D34L1") (pin "DD") (pinfunction "26_DD") (pintype "bidirectional"))
      (node (ref "D34L2") (pin "DD") (pinfunction "26_DD") (pintype "bidirectional"))
      (node (ref "E37") (pin "11") (pinfunction "O_11") (pintype "open_collector"))
    )
    (net (code "222") (name "~{BMB03}") (class "Default")
      (node (ref "D35L1") (pin "T") (pinfunction "16_T") (pintype "bidirectional"))
      (node (ref "D35L2") (pin "T") (pinfunction "16_T") (pintype "bidirectional"))
    )
    (net (code "223") (name "~{BMB04}") (class "Default")
      (node (ref "D35L1") (pin "BB") (pinfunction "24_BB") (pintype "bidirectional"))
      (node (ref "D35L2") (pin "BB") (pinfunction "24_BB") (pintype "bidirectional"))
    )
    (net (code "224") (name "~{BMB05}") (class "Default")
      (node (ref "D35L1") (pin "LL") (pinfunction "32_LL") (pintype "bidirectional"))
      (node (ref "D35L2") (pin "LL") (pinfunction "32_LL") (pintype "bidirectional"))
    )
    (net (code "225") (name "~{BMB06}") (class "Default")
      (node (ref "D35L1") (pin "F") (pinfunction "6_F") (pintype "bidirectional"))
      (node (ref "D35L2") (pin "F") (pinfunction "6_F") (pintype "bidirectional"))
    )
    (net (code "226") (name "~{BMB07}") (class "Default")
      (node (ref "D35L1") (pin "R") (pinfunction "14_R") (pintype "bidirectional"))
      (node (ref "D35L2") (pin "R") (pinfunction "14_R") (pintype "bidirectional"))
    )
    (net (code "227") (name "~{BMB08}") (class "Default")
      (node (ref "D35L1") (pin "Z") (pinfunction "22_Z") (pintype "bidirectional"))
      (node (ref "D35L2") (pin "Z") (pinfunction "22_Z") (pintype "bidirectional"))
    )
    (net (code "228") (name "~{BRUN}") (class "Default")
      (node (ref "D34L1") (pin "JJ") (pinfunction "30_JJ") (pintype "bidirectional"))
      (node (ref "D34L2") (pin "JJ") (pinfunction "30_JJ") (pintype "bidirectional"))
    )
    (net (code "229") (name "~{CLK_PARITY}") (class "Default")
      (node (ref "E17") (pin "6") (pinfunction "CLK_6") (pintype "input"))
      (node (ref "E32") (pin "6") (pinfunction "O_6") (pintype "output"))
      (node (ref "E5") (pin "4") (pinfunction "I0_4") (pintype "input"))
      (node (ref "E5") (pin "5") (pinfunction "I1_5") (pintype "input"))
    )
    (net (code "230") (name "~{DONE}") (class "Default")
      (node (ref "E10") (pin "4") (pinfunction "I1_4") (pintype "input"))
      (node (ref "E25") (pin "4") (pinfunction "O_4") (pintype "output"))
      (node (ref "E31") (pin "12") (pinfunction "I2_12") (pintype "input"))
    )
    (net (code "231") (name "~{ENB_BUF_LD}") (class "Default")
      (node (ref "E21") (pin "9") (pinfunction "S/~{L}_9") (pintype "input"))
      (node (ref "E22") (pin "9") (pinfunction "S/~{L}_9") (pintype "input"))
      (node (ref "E23") (pin "9") (pinfunction "S/~{L}_9") (pintype "input"))
      (node (ref "E24") (pin "11") (pinfunction "O_11") (pintype "output"))
      (node (ref "E32") (pin "13") (pinfunction "I2_13") (pintype "input"))
      (node (ref "E32") (pin "2") (pinfunction "I1_2") (pintype "input"))
      (node (ref "E4") (pin "9") (pinfunction "LD_9") (pintype "input"))
    )
    (net (code "232") (name "~{INIT1}") (class "Default")
      (node (ref "E11") (pin "7") (pinfunction "Y7_7") (pintype "output"))
      (node (ref "E2") (pin "4") (pinfunction "PRE_4") (pintype "input"))
    )
    (net (code "233") (name "~{INIT4}") (class "Default")
      (node (ref "E13") (pin "7") (pinfunction "Y7_7") (pintype "output"))
      (node (ref "E2") (pin "3") (pinfunction "CLK_3") (pintype "input"))
    )
    (net (code "234") (name "~{INIT}") (class "Default")
      (node (ref "E15") (pin "6") (pinfunction "O_6") (pintype "output"))
      (node (ref "E16") (pin "1") (pinfunction "CLR_1") (pintype "input"))
      (node (ref "E16") (pin "13") (pinfunction "CLR_13") (pintype "input"))
      (node (ref "E17") (pin "3") (pinfunction "CLR_3") (pintype "input"))
      (node (ref "E19") (pin "3") (pinfunction "CLR_3") (pintype "input"))
      (node (ref "E19") (pin "8") (pinfunction "CLR_8") (pintype "input"))
      (node (ref "E21") (pin "1") (pinfunction "CLR_1") (pintype "input"))
      (node (ref "E22") (pin "1") (pinfunction "CLR_1") (pintype "input"))
      (node (ref "E23") (pin "1") (pinfunction "CLR_1") (pintype "input"))
      (node (ref "E24") (pin "9") (pinfunction "I0_9") (pintype "input"))
      (node (ref "E30") (pin "1") (pinfunction "CLR_1") (pintype "input"))
      (node (ref "E4") (pin "1") (pinfunction "CLR_1") (pintype "input"))
    )
    (net (code "235") (name "~{INTR4}") (class "Default")
      (node (ref "E13") (pin "9") (pinfunction "Y6_9") (pintype "output"))
      (node (ref "E30") (pin "3") (pinfunction "CLK_3") (pintype "input"))
    )
    (net (code "236") (name "~{INT_RQ}") (class "Default")
      (node (ref "D34L1") (pin "Z") (pinfunction "22_Z") (pintype "bidirectional"))
      (node (ref "D34L2") (pin "Z") (pinfunction "22_Z") (pintype "bidirectional"))
      (node (ref "E33") (pin "3") (pinfunction "O_3") (pintype "open_collector"))
    )
    (net (code "237") (name "~{IOS}") (class "Default")
      (node (ref "D34L1") (pin "V") (pinfunction "18_V") (pintype "bidirectional"))
      (node (ref "D34L2") (pin "V") (pinfunction "18_V") (pintype "bidirectional"))
      (node (ref "E33") (pin "8") (pinfunction "O_8") (pintype "open_collector"))
    )
    (net (code "238") (name "~{LCD1}") (class "Default")
      (node (ref "E10") (pin "9") (pinfunction "I0_9") (pintype "input"))
      (node (ref "E11") (pin "14") (pinfunction "Y1_14") (pintype "output"))
      (node (ref "E16") (pin "11") (pinfunction "CLK_11") (pintype "input"))
      (node (ref "E16") (pin "3") (pinfunction "CLK_3") (pintype "input"))
      (node (ref "E24") (pin "5") (pinfunction "I1_5") (pintype "input"))
      (node (ref "E25") (pin "5") (pinfunction "I_5") (pintype "input"))
    )
    (net (code "239") (name "~{MAINT}") (class "Default")
      (node (ref "E10") (pin "3") (pinfunction "I0_3") (pintype "input"))
      (node (ref "E16") (pin "8") (pinfunction "~{Q}_8") (pintype "output"))
      (node (ref "E17") (pin "2") (pinfunction "PRE_2") (pintype "input"))
      (node (ref "E19") (pin "2") (pinfunction "PRE_2") (pintype "input"))
      (node (ref "E19") (pin "7") (pinfunction "PRE_7") (pintype "input"))
      (node (ref "E24") (pin "13") (pinfunction "I1_13") (pintype "input"))
      (node (ref "E31") (pin "5") (pinfunction "I3_5") (pintype "input"))
      (node (ref "E31") (pin "9") (pinfunction "I0_9") (pintype "input"))
    )
    (net (code "240") (name "~{MYDEV}") (class "Default")
      (node (ref "E11") (pin "4") (pinfunction "G2A_4") (pintype "input"))
      (node (ref "E12") (pin "4") (pinfunction "G2A_4") (pintype "input"))
      (node (ref "E13") (pin "4") (pinfunction "G2A_4") (pintype "input"))
      (node (ref "IOT") (pin "1") (pinfunction "P_1") (pintype "passive"))
    )
    (net (code "241") (name "~{PARITY}") (class "Default")
      (node (ref "E15") (pin "12") (pinfunction "I0_12") (pintype "input"))
      (node (ref "E17") (pin "10") (pinfunction "~{Q}_10") (pintype "output"))
    )
    (net (code "242") (name "~{RX_12_BIT}") (class "Default")
      (node (ref "DRIVE") (pin "FF") (pinfunction "28_FF") (pintype "bidirectional"))
      (node (ref "E37") (pin "8") (pinfunction "O_8") (pintype "open_collector"))
      (node (ref "R16") (pin "2") (pinfunction "2_2") (pintype "passive"))
      (node (ref "R7") (pin "1") (pinfunction "1_1") (pintype "passive"))
    )
    (net (code "243") (name "~{RX_DATA}") (class "Default")
      (node (ref "DRIVE") (pin "BB") (pinfunction "24_BB") (pintype "bidirectional"))
      (node (ref "E35") (pin "2") (pinfunction "I0_2") (pintype "input"))
      (node (ref "E37") (pin "6") (pinfunction "O_6") (pintype "open_collector"))
      (node (ref "R17") (pin "2") (pinfunction "2_2") (pintype "passive"))
      (node (ref "R8") (pin "1") (pinfunction "1_1") (pintype "passive"))
    )
    (net (code "244") (name "~{RX_DONE}") (class "Default")
      (node (ref "DRIVE") (pin "X") (pinfunction "20_X") (pintype "bidirectional"))
      (node (ref "E36") (pin "8") (pinfunction "I0_8") (pintype "input"))
      (node (ref "R13") (pin "2") (pinfunction "2_2") (pintype "passive"))
      (node (ref "R4") (pin "1") (pinfunction "1_1") (pintype "passive"))
    )
    (net (code "245") (name "~{RX_ERROR}") (class "Default")
      (node (ref "DRIVE") (pin "J") (pinfunction "8_J") (pintype "bidirectional"))
      (node (ref "E36") (pin "3") (pinfunction "I1_3") (pintype "input"))
      (node (ref "R14") (pin "2") (pinfunction "2_2") (pintype "passive"))
      (node (ref "R5") (pin "1") (pinfunction "1_1") (pintype "passive"))
    )
    (net (code "246") (name "~{RX_INIT}") (class "Default")
      (node (ref "DRIVE") (pin "N") (pinfunction "12_N") (pintype "bidirectional"))
      (node (ref "E37") (pin "3") (pinfunction "O_3") (pintype "open_collector"))
      (node (ref "R9") (pin "1") (pinfunction "1_1") (pintype "passive"))
    )
    (net (code "247") (name "~{RX_OUT}") (class "Default")
      (node (ref "DRIVE") (pin "RR") (pinfunction "36_RR") (pintype "bidirectional"))
      (node (ref "E35") (pin "8") (pinfunction "I0_8") (pintype "input"))
      (node (ref "R12") (pin "2") (pinfunction "2_2") (pintype "passive"))
      (node (ref "R3") (pin "1") (pinfunction "1_1") (pintype "passive"))
    )
    (net (code "248") (name "~{RX_RUN}") (class "Default")
      (node (ref "DRIVE") (pin "D") (pinfunction "4_D") (pintype "bidirectional"))
      (node (ref "E33") (pin "11") (pinfunction "O_11") (pintype "open_collector"))
      (node (ref "R15") (pin "2") (pinfunction "2_2") (pintype "passive"))
      (node (ref "R6") (pin "1") (pinfunction "1_1") (pintype "passive"))
    )
    (net (code "249") (name "~{RX_SHIFT}") (class "Default")
      (node (ref "DRIVE") (pin "LL") (pinfunction "32_LL") (pintype "bidirectional"))
      (node (ref "E35") (pin "5") (pinfunction "I0_5") (pintype "input"))
      (node (ref "R10") (pin "2") (pinfunction "2_2") (pintype "passive"))
      (node (ref "R2") (pin "1") (pinfunction "1_1") (pintype "passive"))
    )
    (net (code "250") (name "~{RX_TR_REQ}") (class "Default")
      (node (ref "DRIVE") (pin "T") (pinfunction "16_T") (pintype "bidirectional"))
      (node (ref "E36") (pin "5") (pinfunction "I0_5") (pintype "input"))
      (node (ref "R1") (pin "1") (pinfunction "1_1") (pintype "passive"))
      (node (ref "R11") (pin "2") (pinfunction "2_2") (pintype "passive"))
    )
    (net (code "251") (name "~{SDN4}") (class "Default")
      (node (ref "E13") (pin "10") (pinfunction "Y5_10") (pintype "output"))
      (node (ref "E18") (pin "8") (pinfunction "I0_8") (pintype "input"))
    )
    (net (code "252") (name "~{SER4}") (class "Default")
      (node (ref "E13") (pin "11") (pinfunction "Y4_11") (pintype "output"))
      (node (ref "E18") (pin "5") (pinfunction "I0_5") (pintype "input"))
    )
    (net (code "253") (name "~{STR2}") (class "Default")
      (node (ref "E12") (pin "12") (pinfunction "Y3_12") (pintype "output"))
      (node (ref "E18") (pin "2") (pinfunction "I0_2") (pintype "input"))
    )
    (net (code "254") (name "~{XDR2}") (class "Default")
      (node (ref "E12") (pin "13") (pinfunction "Y2_13") (pintype "output"))
      (node (ref "E24") (pin "4") (pinfunction "I0_4") (pintype "input"))
      (node (ref "E25") (pin "9") (pinfunction "I_9") (pintype "input"))
      (node (ref "E35") (pin "12") (pinfunction "I1_12") (pintype "input"))
      (node (ref "E5") (pin "10") (pinfunction "I1_10") (pintype "input"))
      (node (ref "E5") (pin "9") (pinfunction "I0_9") (pintype "input"))
    )
  )
)
